# LoraGateway.net
KiCad netlist of a schematic drawn in EAGLE
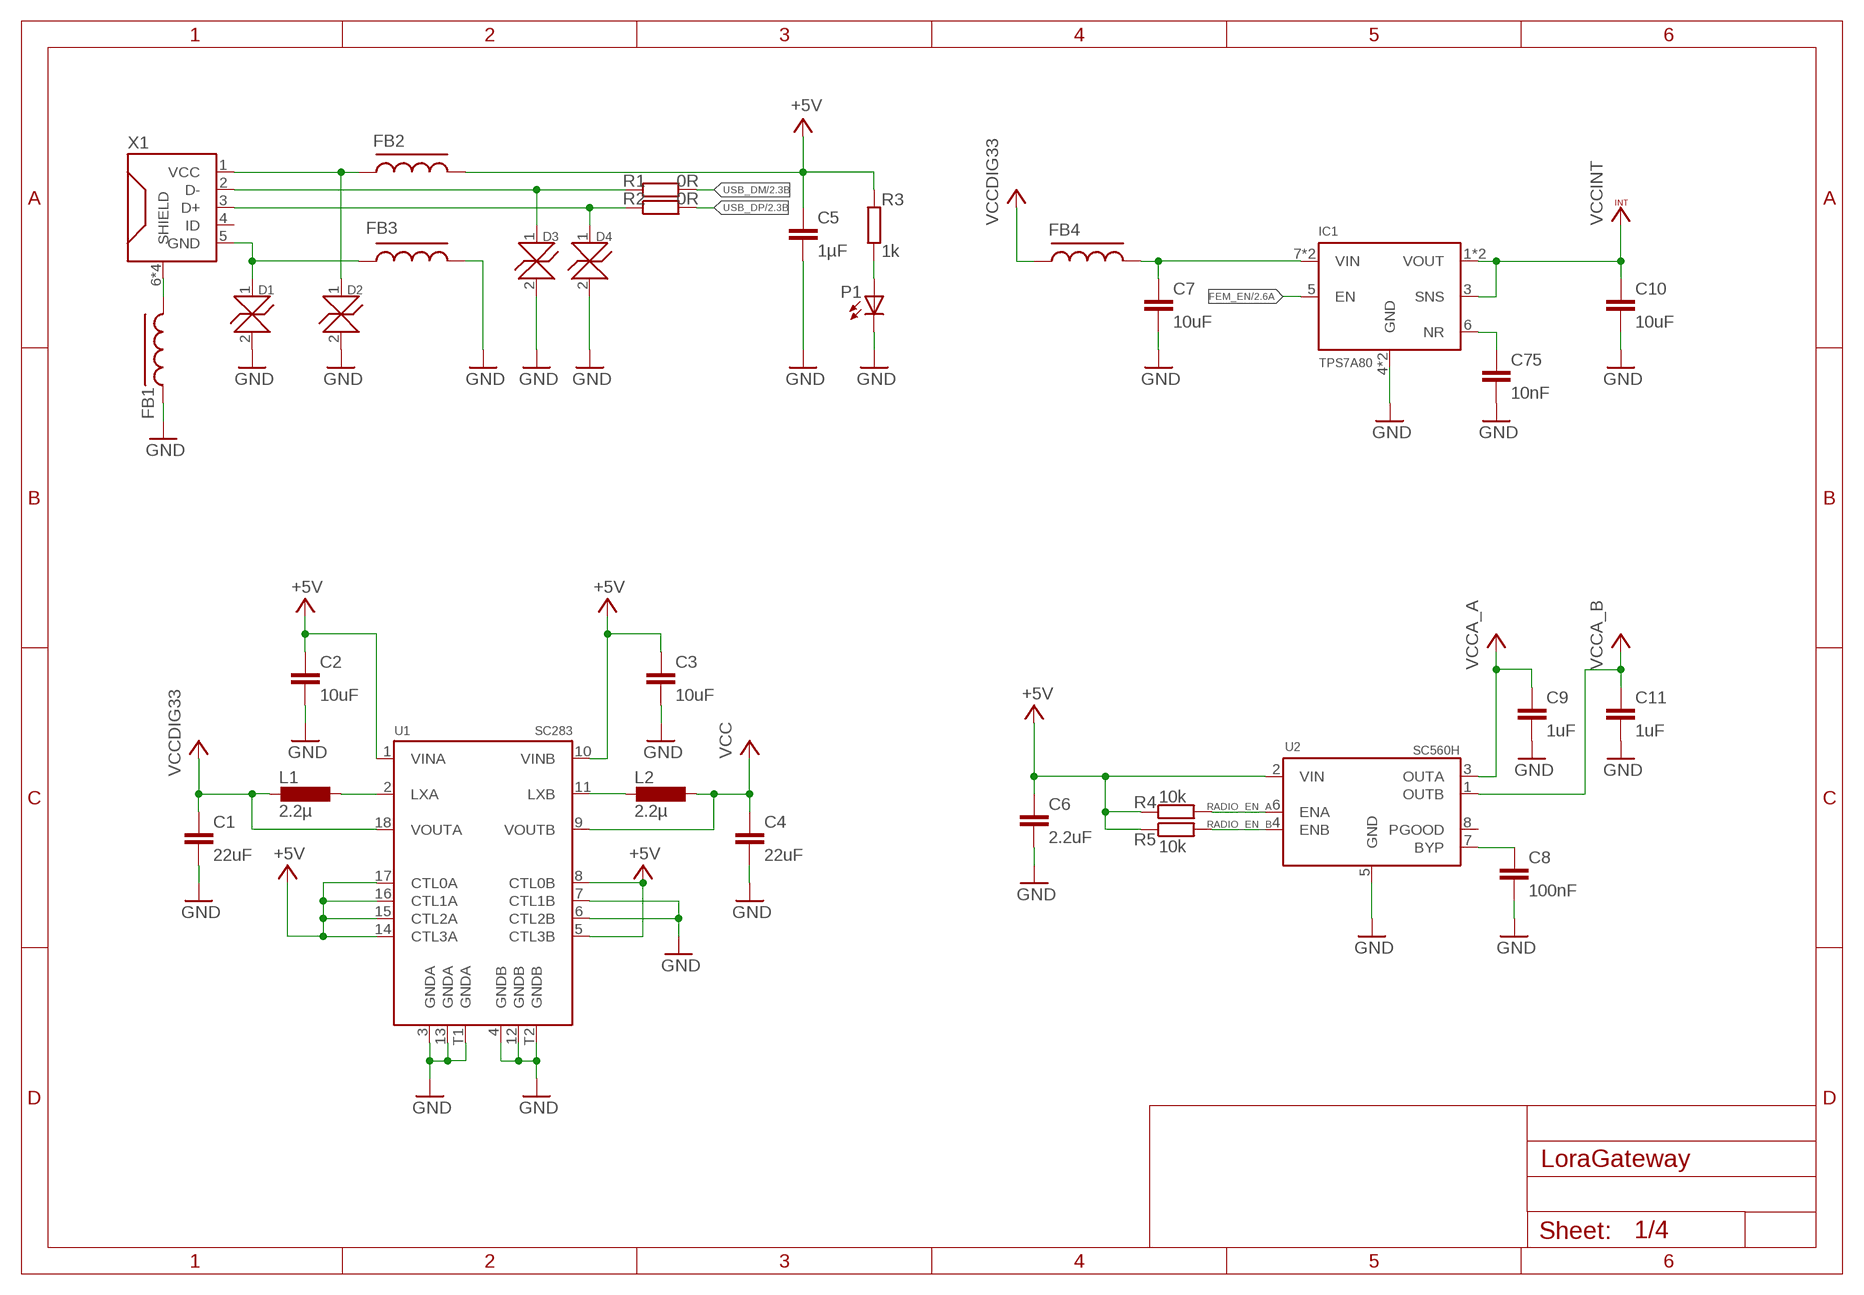
[diagram p0: schematic, sheet 1]
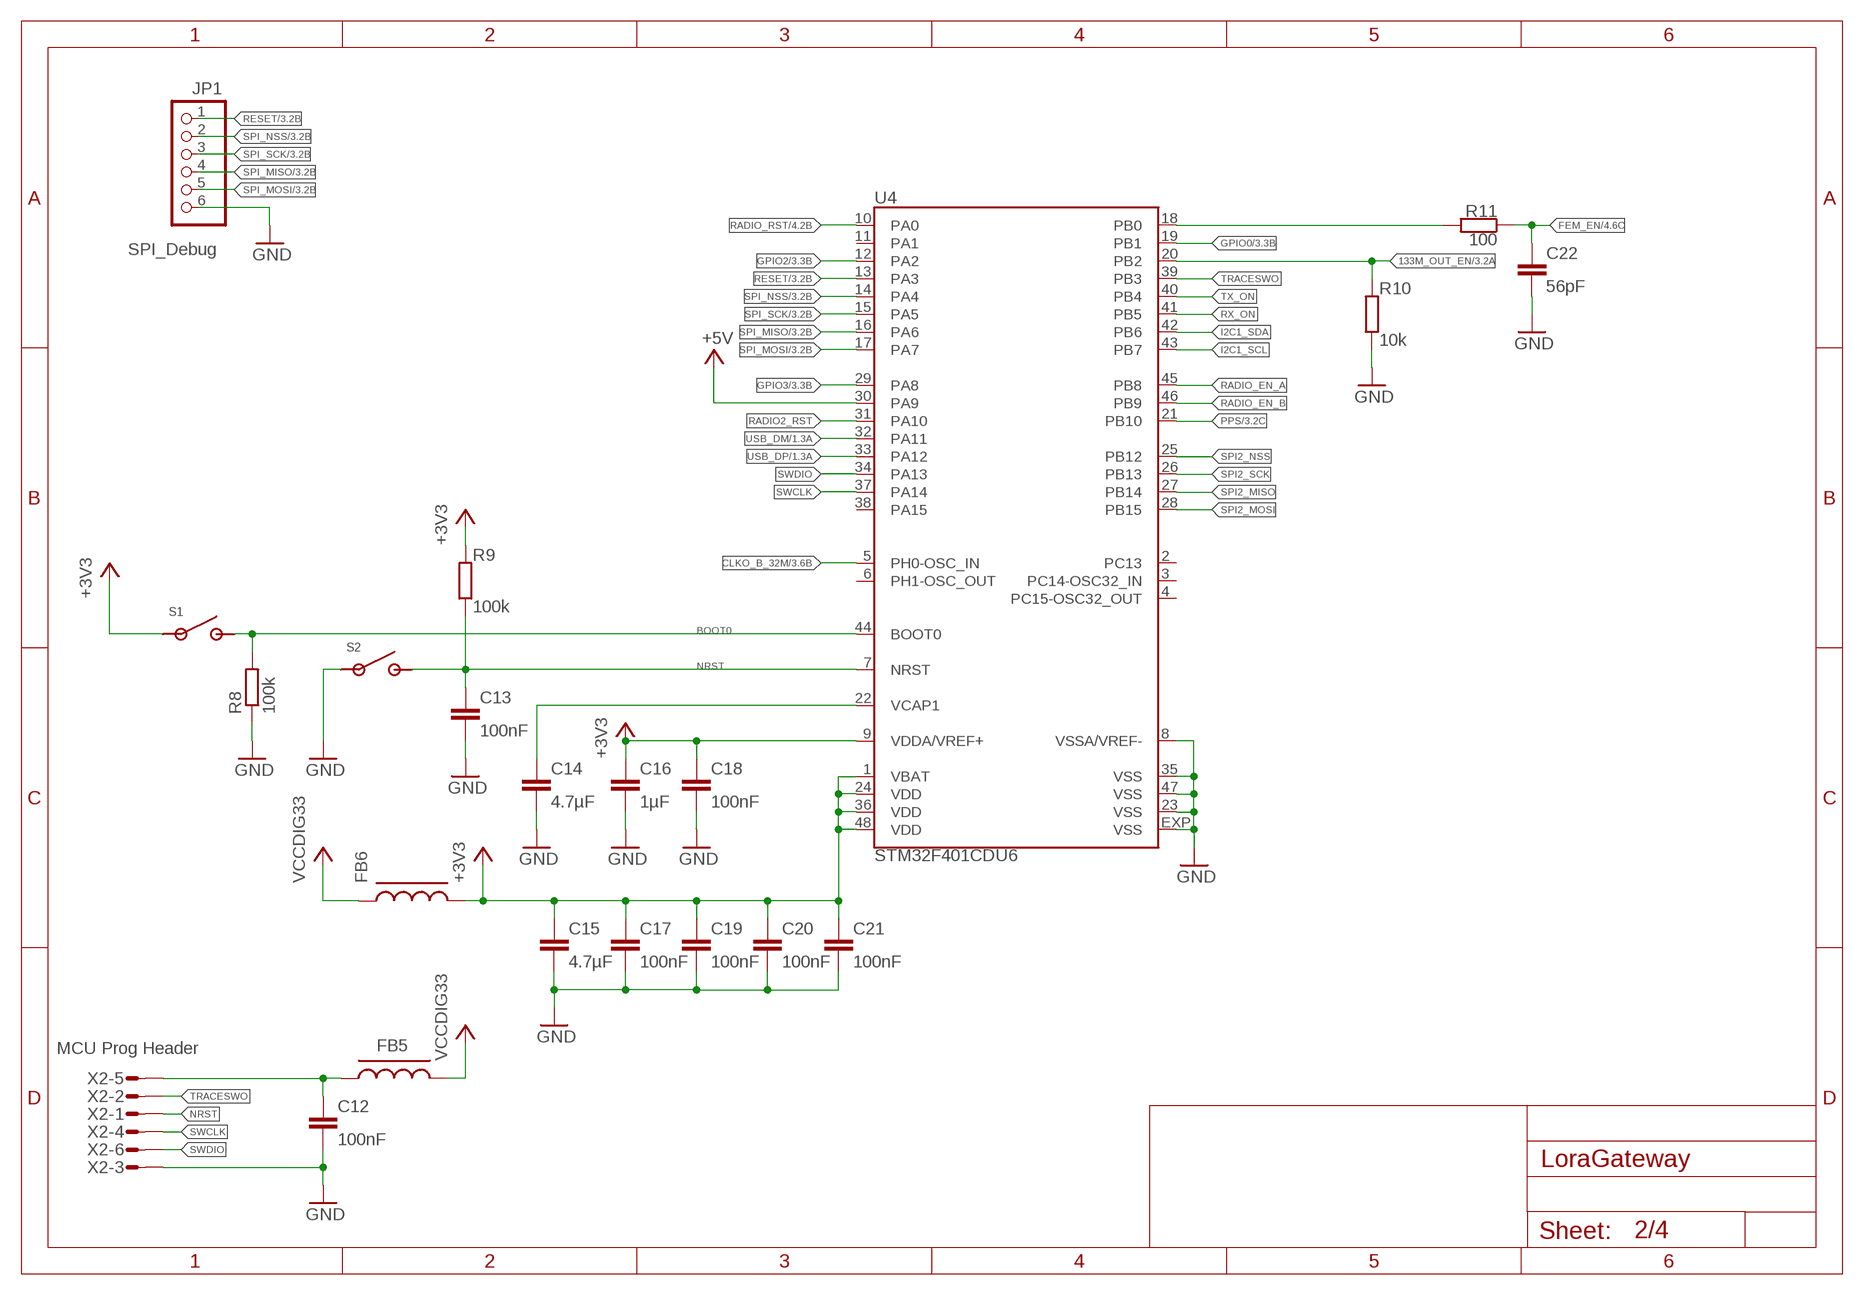
[diagram p1: schematic, sheet 2]
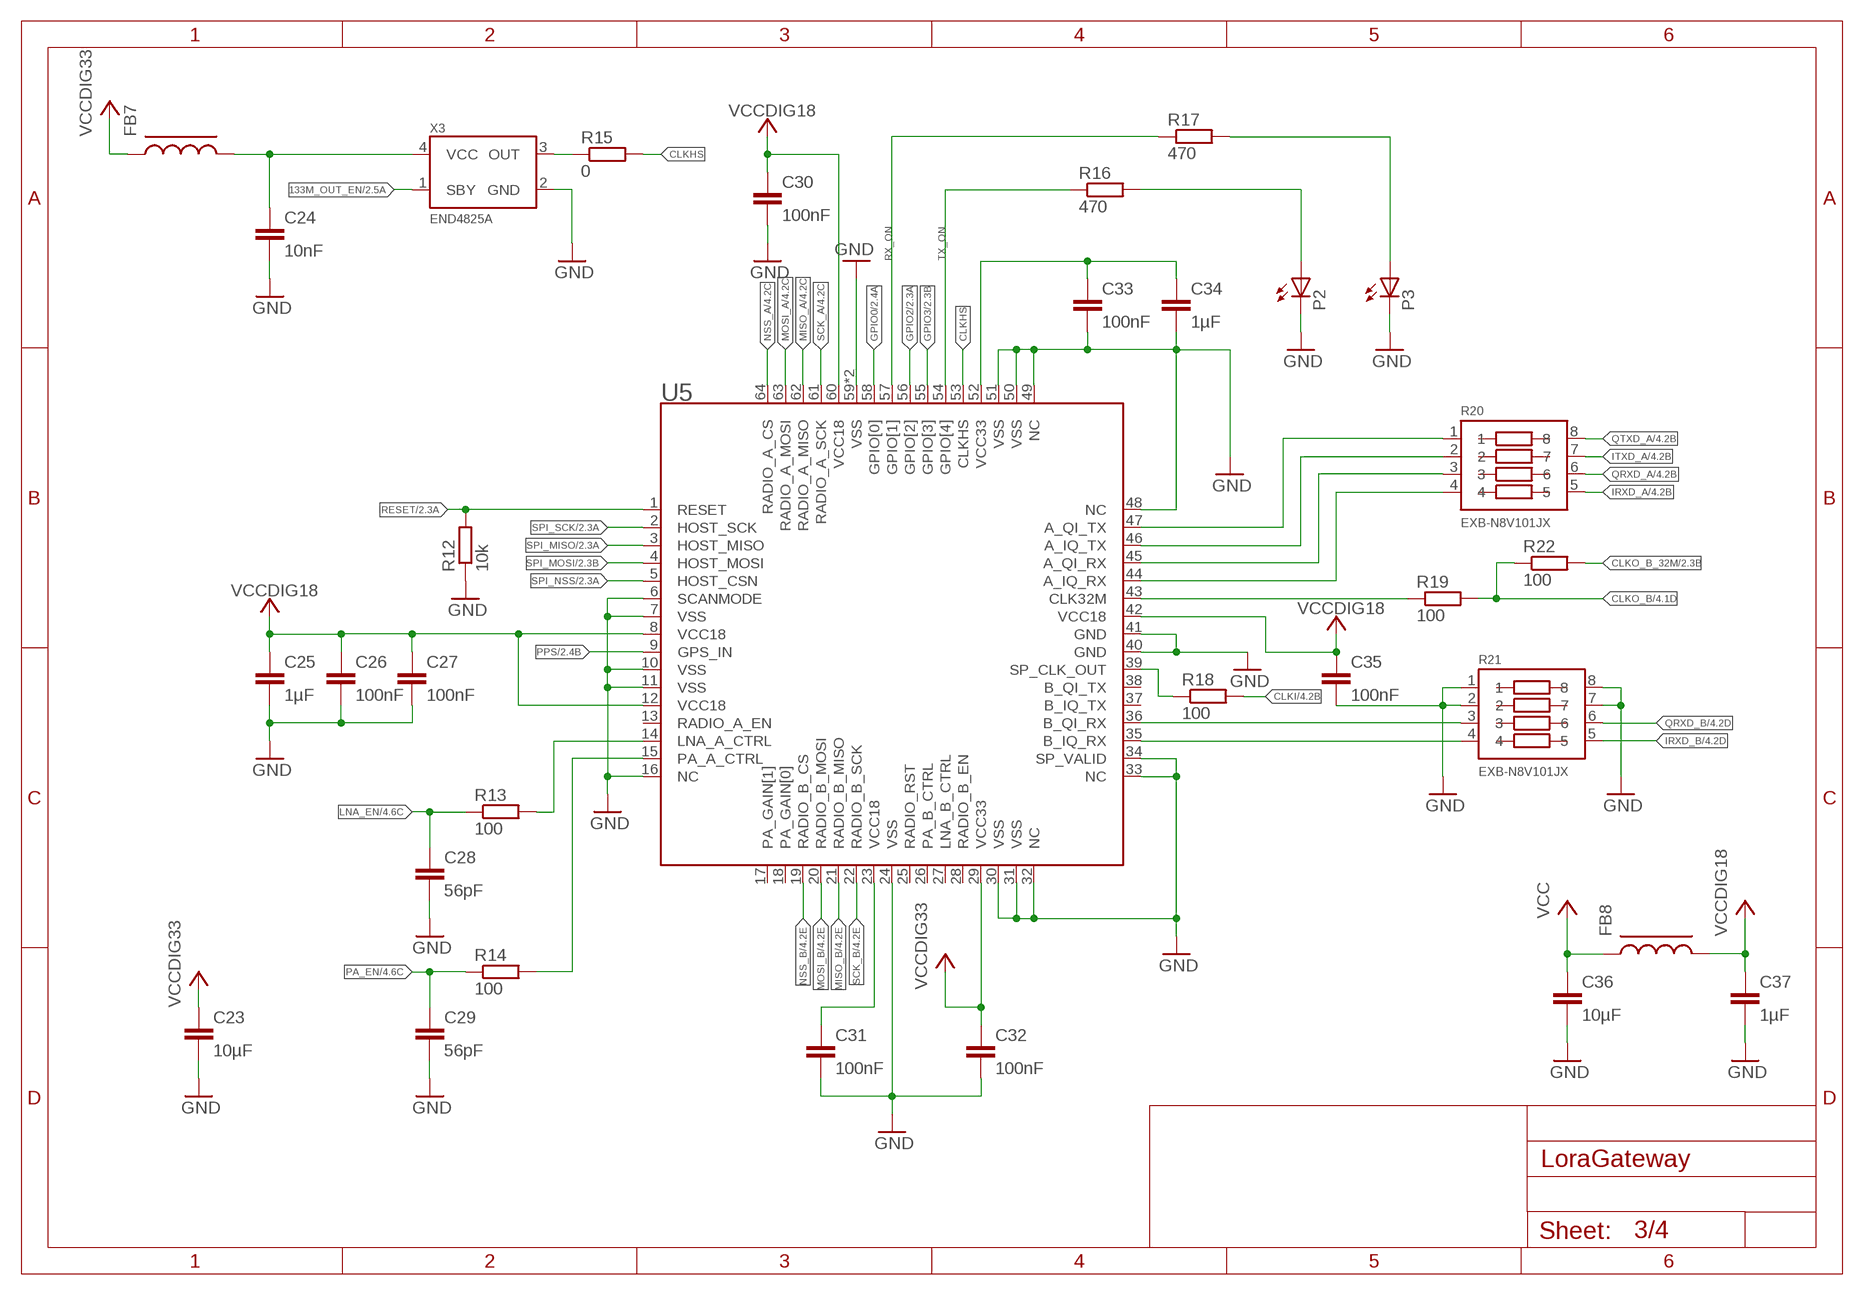
[diagram p2: schematic, sheet 3]
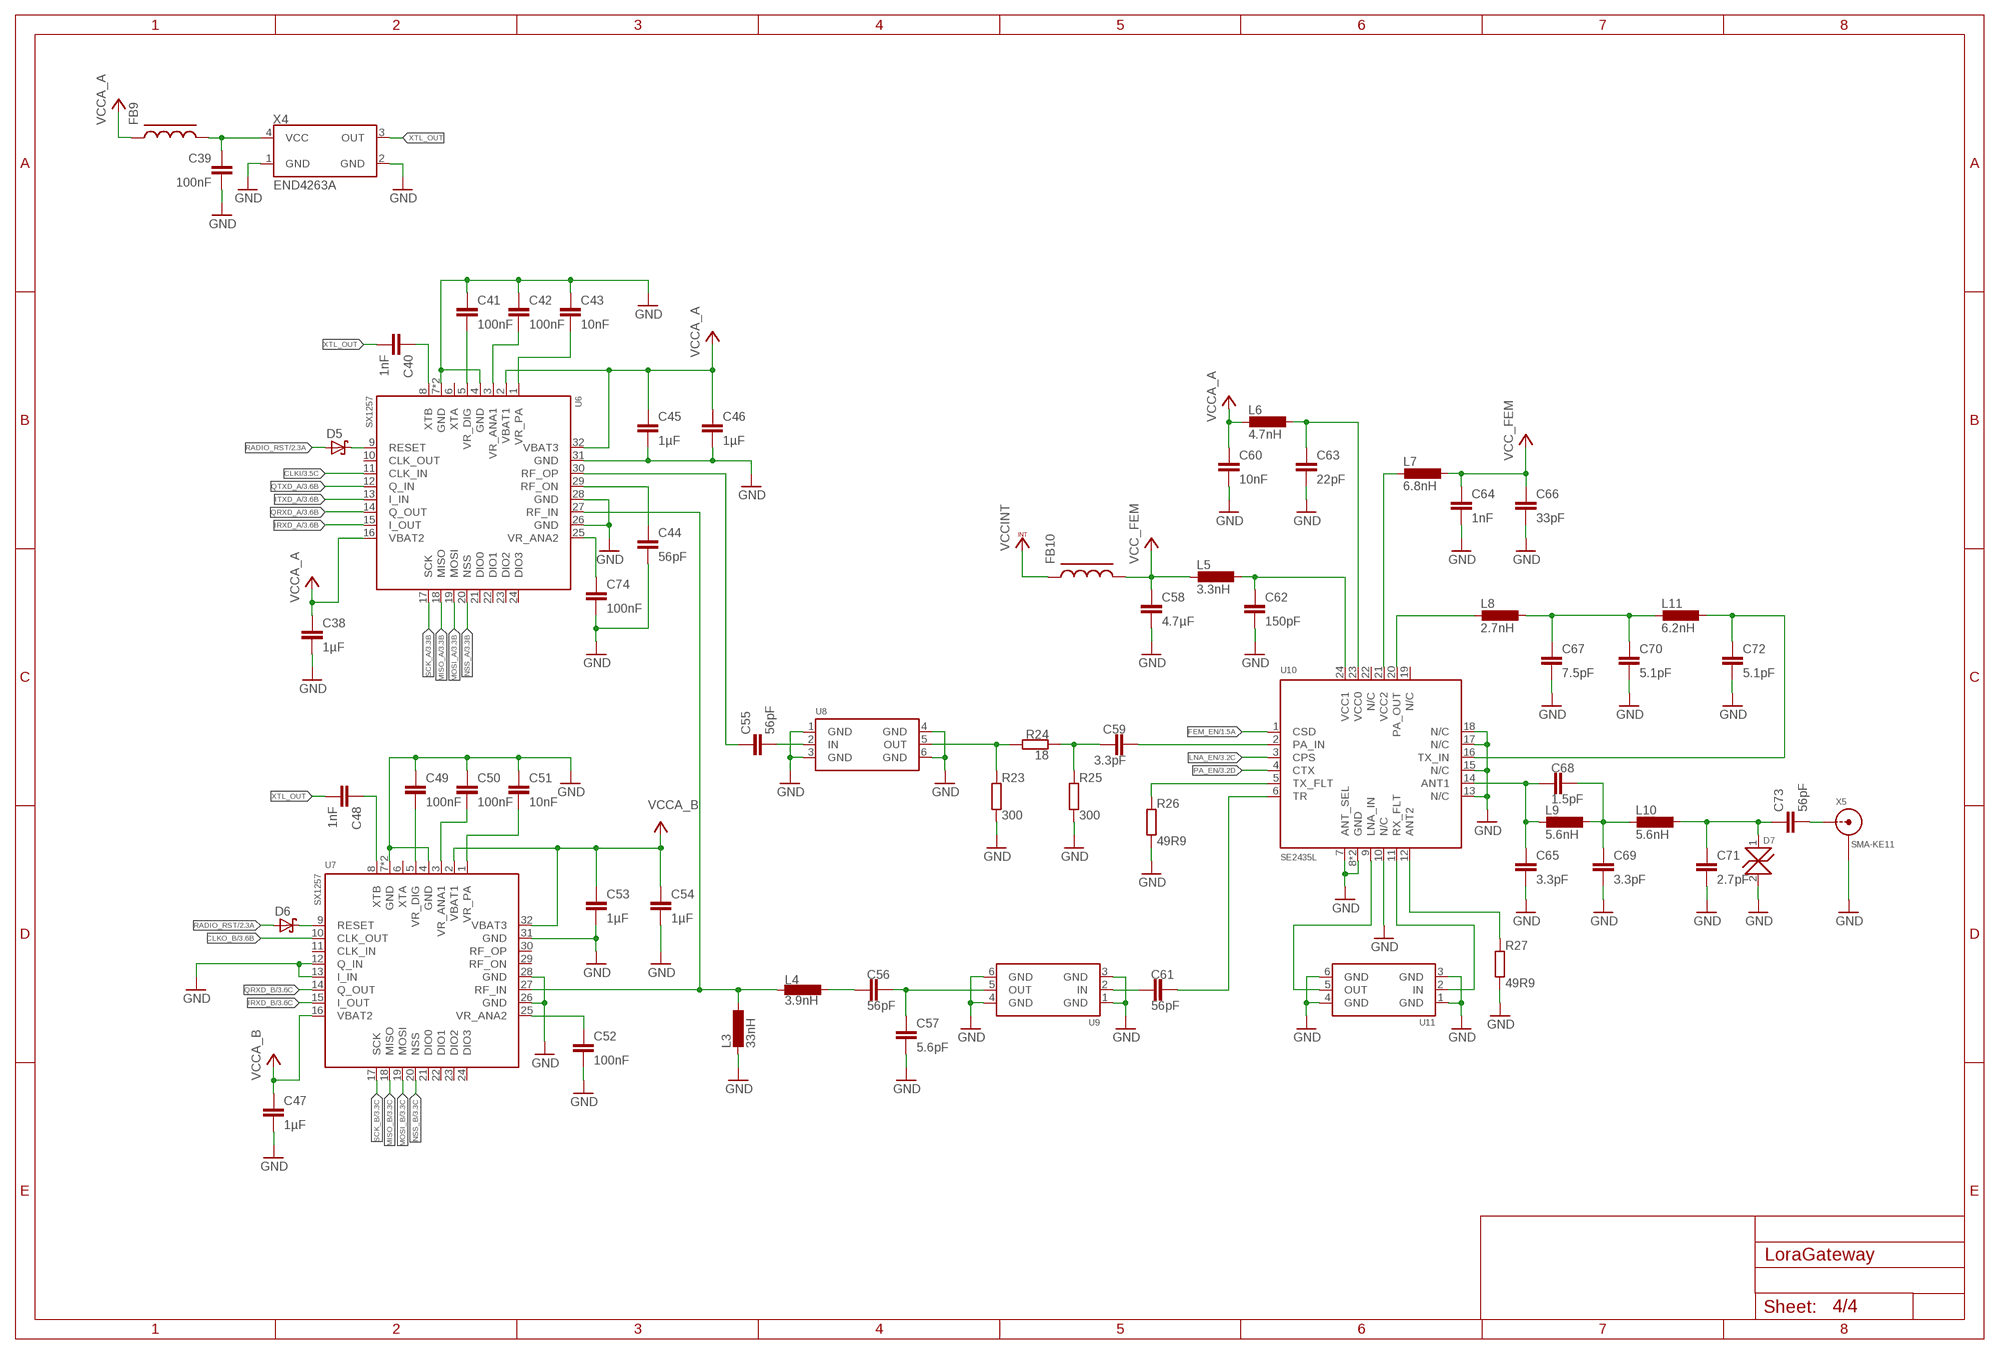
[diagram p3: schematic, sheet 4]

(export (version "E")
  (design (tool "Eeschema 10.0.6"))
  (components
    (comp (ref "C38")
      (value "1µF")
      (footprint "eagle-import:C0603")
      (libsource (lib "eagle-import") (part "C-EUC0603"))
    )
    (comp (ref "C39")
      (value "100nF")
      (footprint "eagle-import:C0402")
      (libsource (lib "eagle-import") (part "C-EUC0402"))
    )
    (comp (ref "C40")
      (value "1nF")
      (footprint "eagle-import:C0402")
      (fields (field (name "OC_DIGIKEY") "490-6348-1-ND"))
      (libsource (lib "eagle-import") (part "C-EUC0402"))
    )
    (comp (ref "C41")
      (value "100nF")
      (footprint "eagle-import:C0402")
      (libsource (lib "eagle-import") (part "C-EUC0402"))
    )
    (comp (ref "C42")
      (value "100nF")
      (footprint "eagle-import:C0402")
      (libsource (lib "eagle-import") (part "C-EUC0402"))
    )
    (comp (ref "C43")
      (value "10nF")
      (footprint "eagle-import:C0402")
      (libsource (lib "eagle-import") (part "C-EUC0402"))
    )
    (comp (ref "C44")
      (value "56pF")
      (footprint "eagle-import:C0402")
      (libsource (lib "eagle-import") (part "C-EUC0402"))
    )
    (comp (ref "C45")
      (value "1µF")
      (footprint "eagle-import:C0603")
      (libsource (lib "eagle-import") (part "C-EUC0603"))
    )
    (comp (ref "C46")
      (value "1µF")
      (footprint "eagle-import:C0603")
      (libsource (lib "eagle-import") (part "C-EUC0603"))
    )
    (comp (ref "C47")
      (value "1µF")
      (footprint "eagle-import:C0603")
      (libsource (lib "eagle-import") (part "C-EUC0603"))
    )
    (comp (ref "C48")
      (value "1nF")
      (footprint "eagle-import:C0402")
      (libsource (lib "eagle-import") (part "C-EUC0402"))
    )
    (comp (ref "C49")
      (value "100nF")
      (footprint "eagle-import:C0402")
      (libsource (lib "eagle-import") (part "C-EUC0402"))
    )
    (comp (ref "C50")
      (value "100nF")
      (footprint "eagle-import:C0402")
      (libsource (lib "eagle-import") (part "C-EUC0402"))
    )
    (comp (ref "C51")
      (value "10nF")
      (footprint "eagle-import:C0402")
      (libsource (lib "eagle-import") (part "C-EUC0402"))
    )
    (comp (ref "C52")
      (value "100nF")
      (footprint "eagle-import:C0402")
      (libsource (lib "eagle-import") (part "C-EUC0402"))
    )
    (comp (ref "C53")
      (value "1µF")
      (footprint "eagle-import:C0603")
      (libsource (lib "eagle-import") (part "C-EUC0603"))
    )
    (comp (ref "C54")
      (value "1µF")
      (footprint "eagle-import:C0603")
      (libsource (lib "eagle-import") (part "C-EUC0603"))
    )
    (comp (ref "C55")
      (value "56pF")
      (footprint "eagle-import:C0402")
      (libsource (lib "eagle-import") (part "C-EUC0402"))
    )
    (comp (ref "C56")
      (value "56pF")
      (footprint "eagle-import:C0402")
      (libsource (lib "eagle-import") (part "C-EUC0402"))
    )
    (comp (ref "C57")
      (value "5.6pF")
      (footprint "eagle-import:C0402")
      (libsource (lib "eagle-import") (part "C-EUC0402"))
    )
    (comp (ref "C58")
      (value "4.7µF")
      (footprint "eagle-import:C0603")
      (libsource (lib "eagle-import") (part "C-EUC0603"))
    )
    (comp (ref "C59")
      (value "3.3pF")
      (footprint "eagle-import:C0402")
      (libsource (lib "eagle-import") (part "C-EUC0402"))
    )
    (comp (ref "C60")
      (value "10nF")
      (footprint "eagle-import:C0402")
      (libsource (lib "eagle-import") (part "C-EUC0402"))
    )
    (comp (ref "C61")
      (value "56pF")
      (footprint "eagle-import:C0402")
      (libsource (lib "eagle-import") (part "C-EUC0402"))
    )
    (comp (ref "C62")
      (value "150pF")
      (footprint "eagle-import:C0402")
      (libsource (lib "eagle-import") (part "C-EUC0402"))
    )
    (comp (ref "C63")
      (value "22pF")
      (footprint "eagle-import:C0402")
      (libsource (lib "eagle-import") (part "C-EUC0402"))
    )
    (comp (ref "C64")
      (value "1nF")
      (footprint "eagle-import:C0402")
      (libsource (lib "eagle-import") (part "C-EUC0402"))
    )
    (comp (ref "C65")
      (value "3.3pF")
      (footprint "eagle-import:C0402")
      (libsource (lib "eagle-import") (part "C-EUC0402"))
    )
    (comp (ref "C66")
      (value "33pF")
      (footprint "eagle-import:C0402")
      (libsource (lib "eagle-import") (part "C-EUC0402"))
    )
    (comp (ref "C67")
      (value "7.5pF")
      (footprint "eagle-import:C0402")
      (libsource (lib "eagle-import") (part "C-EUC0402"))
    )
    (comp (ref "C68")
      (value "1.5pF")
      (footprint "eagle-import:C0402")
      (libsource (lib "eagle-import") (part "C-EUC0402"))
    )
    (comp (ref "C69")
      (value "3.3pF")
      (footprint "eagle-import:C0402")
      (libsource (lib "eagle-import") (part "C-EUC0402"))
    )
    (comp (ref "C70")
      (value "5.1pF")
      (footprint "eagle-import:C0402")
      (libsource (lib "eagle-import") (part "C-EUC0402"))
    )
    (comp (ref "C71")
      (value "2.7pF")
      (footprint "eagle-import:C0402")
      (libsource (lib "eagle-import") (part "C-EUC0402"))
    )
    (comp (ref "C72")
      (value "5.1pF")
      (footprint "eagle-import:C0402")
      (libsource (lib "eagle-import") (part "C-EUC0402"))
    )
    (comp (ref "C73")
      (value "56pF")
      (footprint "eagle-import:C0402")
      (libsource (lib "eagle-import") (part "C-EUC0402"))
    )
    (comp (ref "C74")
      (value "100nF")
      (footprint "eagle-import:C0402")
      (libsource (lib "eagle-import") (part "C-EUC0402"))
    )
    (comp (ref "D5")
      (value "BAT54XV2T1G")
      (footprint "eagle-import:SOD523")
      (libsource (lib "eagle-import") (part "BAT54XV2T1G"))
    )
    (comp (ref "D6")
      (value "BAT54XV2T1G")
      (footprint "eagle-import:SOD523")
      (libsource (lib "eagle-import") (part "BAT54XV2T1G"))
    )
    (comp (ref "D7")
      (value "LXES15AAA1-153")
      (footprint "eagle-import:LXES15AAA1-153")
      (libsource (lib "eagle-import") (part "LXES15AAA1-153"))
    )
    (comp (ref "FB9")
      (value "BLM15PG100SN1D0402")
      (footprint "eagle-import:L0402")
      (libsource (lib "eagle-import") (part "BLM15PG100SN1D0402"))
    )
    (comp (ref "FB10")
      (value "BLM18PG121SH1D")
      (footprint "eagle-import:L0603")
      (libsource (lib "eagle-import") (part "BLM18PG121SH1D"))
    )
    (comp (ref "L3")
      (value "33nH")
      (footprint "eagle-import:L0402")
      (libsource (lib "eagle-import") (part "L-EU0402"))
    )
    (comp (ref "L4")
      (value "3.9nH")
      (footprint "eagle-import:L0402")
      (libsource (lib "eagle-import") (part "L-EU0402"))
    )
    (comp (ref "L5")
      (value "3.3nH")
      (footprint "eagle-import:L0402")
      (libsource (lib "eagle-import") (part "L-EU0402"))
    )
    (comp (ref "L6")
      (value "4.7nH")
      (footprint "eagle-import:L0402")
      (libsource (lib "eagle-import") (part "L-EU0402"))
    )
    (comp (ref "L7")
      (value "6.8nH")
      (footprint "eagle-import:L0402")
      (libsource (lib "eagle-import") (part "L-EU0402"))
    )
    (comp (ref "L8")
      (value "2.7nH")
      (footprint "eagle-import:L0402")
      (libsource (lib "eagle-import") (part "L-EU0402"))
    )
    (comp (ref "L9")
      (value "5.6nH")
      (footprint "eagle-import:L0402")
      (libsource (lib "eagle-import") (part "L-EU0402"))
    )
    (comp (ref "L10")
      (value "5.6nH")
      (footprint "eagle-import:L0402")
      (libsource (lib "eagle-import") (part "L-EU0402"))
    )
    (comp (ref "L11")
      (value "6.2nH")
      (footprint "eagle-import:L0402")
      (libsource (lib "eagle-import") (part "L-EU0402"))
    )
    (comp (ref "R23")
      (value "300")
      (footprint "eagle-import:R0402")
      (libsource (lib "eagle-import") (part "R-EU_R0402"))
    )
    (comp (ref "R24")
      (value "18")
      (footprint "eagle-import:R0402")
      (libsource (lib "eagle-import") (part "R-EU_R0402"))
    )
    (comp (ref "R25")
      (value "300")
      (footprint "eagle-import:R0402")
      (libsource (lib "eagle-import") (part "R-EU_R0402"))
    )
    (comp (ref "R26")
      (value "49R9")
      (footprint "eagle-import:R0402")
      (libsource (lib "eagle-import") (part "R-EU_R0402"))
    )
    (comp (ref "R27")
      (value "49R9")
      (footprint "eagle-import:R0402")
      (libsource (lib "eagle-import") (part "R-EU_R0402"))
    )
    (comp (ref "U6")
      (value "SX1257")
      (footprint "eagle-import:QFN32")
      (libsource (lib "eagle-import") (part "SX1257"))
    )
    (comp (ref "U7")
      (value "SX1257")
      (footprint "eagle-import:QFN32")
      (libsource (lib "eagle-import") (part "SX1257"))
    )
    (comp (ref "U8")
      (value "B39871B3717U410")
      (footprint "eagle-import:DCC6C-3X3")
      (libsource (lib "eagle-import") (part "B39871B3717U410"))
    )
    (comp (ref "U9")
      (value "B39871B3717U410")
      (footprint "eagle-import:DCC6C-3X3")
      (libsource (lib "eagle-import") (part "B39871B3717U410"))
    )
    (comp (ref "U10")
      (value "SE2435L")
      (footprint "eagle-import:VQFN24-4X4")
      (libsource (lib "eagle-import") (part "SE2435L"))
    )
    (comp (ref "U11")
      (value "B39871B3717U410")
      (footprint "eagle-import:DCC6C-3X3")
      (libsource (lib "eagle-import") (part "B39871B3717U410"))
    )
    (comp (ref "X4")
      (value "END4263A")
      (footprint "eagle-import:2.0X1.6MM")
      (libsource (lib "eagle-import") (part "END4263A"))
    )
    (comp (ref "X5")
      (value "SMA-KE11")
      (footprint "eagle-import:J502-ND-142-0711-871_876")
      (libsource (lib "eagle-import") (part "SMA-KE11"))
    )
    (comp (ref "C1")
      (value "22uF")
      (footprint "eagle-import:C1206")
      (libsource (lib "eagle-import") (part "C-EUC1206"))
    )
    (comp (ref "C2")
      (value "10uF")
      (footprint "eagle-import:C1206")
      (libsource (lib "eagle-import") (part "C-EUC1206"))
    )
    (comp (ref "C3")
      (value "10uF")
      (footprint "eagle-import:C1206")
      (libsource (lib "eagle-import") (part "C-EUC1206"))
    )
    (comp (ref "C4")
      (value "22uF")
      (footprint "eagle-import:C1206")
      (libsource (lib "eagle-import") (part "C-EUC1206"))
    )
    (comp (ref "C5")
      (value "1µF")
      (footprint "eagle-import:C0805")
      (libsource (lib "eagle-import") (part "C-EUC0805"))
    )
    (comp (ref "C6")
      (value "2.2uF")
      (footprint "eagle-import:C0603")
      (libsource (lib "eagle-import") (part "C-EUC0603"))
    )
    (comp (ref "C7")
      (value "10uF")
      (footprint "eagle-import:C0805")
      (libsource (lib "eagle-import") (part "C-EUC0805"))
    )
    (comp (ref "C8")
      (value "100nF")
      (footprint "eagle-import:C0402")
      (libsource (lib "eagle-import") (part "C-EUC0402"))
    )
    (comp (ref "C9")
      (value "1uF")
      (footprint "eagle-import:C0805")
      (libsource (lib "eagle-import") (part "C-EUC0805"))
    )
    (comp (ref "C10")
      (value "10uF")
      (footprint "eagle-import:C0805")
      (libsource (lib "eagle-import") (part "C-EUC0805"))
    )
    (comp (ref "C11")
      (value "1uF")
      (footprint "eagle-import:C0805")
      (libsource (lib "eagle-import") (part "C-EUC0805"))
    )
    (comp (ref "C75")
      (value "10nF")
      (footprint "eagle-import:C0402")
      (libsource (lib "eagle-import") (part "C-EUC0402"))
    )
    (comp (ref "D1")
      (value "RCLAMP0531T")
      (footprint "eagle-import:SLP1006P2T")
      (libsource (lib "eagle-import") (part "RCLAMP0531T"))
    )
    (comp (ref "D2")
      (value "RCLAMP0531T")
      (footprint "eagle-import:SLP1006P2T")
      (libsource (lib "eagle-import") (part "RCLAMP0531T"))
    )
    (comp (ref "D3")
      (value "RCLAMP0531T")
      (footprint "eagle-import:SLP1006P2T")
      (libsource (lib "eagle-import") (part "RCLAMP0531T"))
    )
    (comp (ref "D4")
      (value "RCLAMP0531T")
      (footprint "eagle-import:SLP1006P2T")
      (libsource (lib "eagle-import") (part "RCLAMP0531T"))
    )
    (comp (ref "FB1")
      (value "BLM15PG100SN1D0402")
      (footprint "eagle-import:L0402")
      (libsource (lib "eagle-import") (part "BLM15PG100SN1D0402"))
    )
    (comp (ref "FB2")
      (value "BLM15PG100SN1D0402")
      (footprint "eagle-import:L0402")
      (libsource (lib "eagle-import") (part "BLM15PG100SN1D0402"))
    )
    (comp (ref "FB3")
      (value "BLM15PG100SN1D0402")
      (footprint "eagle-import:L0402")
      (libsource (lib "eagle-import") (part "BLM15PG100SN1D0402"))
    )
    (comp (ref "FB4")
      (value "BLM15PG100SN1D0402")
      (footprint "eagle-import:L0402")
      (libsource (lib "eagle-import") (part "BLM15PG100SN1D0402"))
    )
    (comp (ref "IC1")
      (value "TPS7A80")
      (footprint "eagle-import:SON-8")
      (libsource (lib "eagle-import") (part "TPS7A80"))
    )
    (comp (ref "L1")
      (value "2.2µ")
      (footprint "eagle-import:ASPI-0418")
      (libsource (lib "eagle-import") (part "ASPI-0418"))
    )
    (comp (ref "L2")
      (value "2.2µ")
      (footprint "eagle-import:ASPI-0418")
      (libsource (lib "eagle-import") (part "ASPI-0418"))
    )
    (comp (ref "P1")
      (value "LTST-C191KGKT")
      (footprint "eagle-import:LED_SML0603")
      (libsource (lib "eagle-import") (part "LTST-C191KGKT"))
    )
    (comp (ref "R1")
      (value "0R")
      (footprint "eagle-import:R0402")
      (libsource (lib "eagle-import") (part "R-EU_R0402"))
    )
    (comp (ref "R2")
      (value "0R")
      (footprint "eagle-import:R0402")
      (libsource (lib "eagle-import") (part "R-EU_R0402"))
    )
    (comp (ref "R3")
      (value "1k")
      (footprint "eagle-import:R0402")
      (libsource (lib "eagle-import") (part "R-EU_R0402"))
    )
    (comp (ref "R4")
      (value "10k")
      (footprint "eagle-import:R0402")
      (libsource (lib "eagle-import") (part "R-EU_R0402"))
    )
    (comp (ref "R5")
      (value "10k")
      (footprint "eagle-import:R0402")
      (libsource (lib "eagle-import") (part "R-EU_R0402"))
    )
    (comp (ref "U1")
      (value "SC283")
      (footprint "eagle-import:2X3MLPQ-W18")
      (libsource (lib "eagle-import") (part "SC283"))
    )
    (comp (ref "U2")
      (value "SC560H")
      (footprint "eagle-import:MLPQ-UT8")
      (libsource (lib "eagle-import") (part "SC560H"))
    )
    (comp (ref "X1")
      (value "USB2-MICRO")
      (footprint "eagle-import:USB-2-MICRO")
      (libsource (lib "eagle-import") (part "USB2-MICRO"))
    )
    (comp (ref "C23")
      (value "10µF")
      (footprint "eagle-import:C0805")
      (libsource (lib "eagle-import") (part "C-EUC0805"))
    )
    (comp (ref "C24")
      (value "10nF")
      (footprint "eagle-import:C0402")
      (libsource (lib "eagle-import") (part "C-EUC0402"))
    )
    (comp (ref "C25")
      (value "1µF")
      (footprint "eagle-import:C0603")
      (libsource (lib "eagle-import") (part "C-EUC0603"))
    )
    (comp (ref "C26")
      (value "100nF")
      (footprint "eagle-import:C0402")
      (libsource (lib "eagle-import") (part "C-EUC0402"))
    )
    (comp (ref "C27")
      (value "100nF")
      (footprint "eagle-import:C0402")
      (libsource (lib "eagle-import") (part "C-EUC0402"))
    )
    (comp (ref "C28")
      (value "56pF")
      (footprint "eagle-import:C0402")
      (libsource (lib "eagle-import") (part "C-EUC0402"))
    )
    (comp (ref "C29")
      (value "56pF")
      (footprint "eagle-import:C0402")
      (libsource (lib "eagle-import") (part "C-EUC0402"))
    )
    (comp (ref "C30")
      (value "100nF")
      (footprint "eagle-import:C0402")
      (libsource (lib "eagle-import") (part "C-EUC0402"))
    )
    (comp (ref "C31")
      (value "100nF")
      (footprint "eagle-import:C0402")
      (libsource (lib "eagle-import") (part "C-EUC0402"))
    )
    (comp (ref "C32")
      (value "100nF")
      (footprint "eagle-import:C0402")
      (libsource (lib "eagle-import") (part "C-EUC0402"))
    )
    (comp (ref "C33")
      (value "100nF")
      (footprint "eagle-import:C0402")
      (libsource (lib "eagle-import") (part "C-EUC0402"))
    )
    (comp (ref "C34")
      (value "1µF")
      (footprint "eagle-import:C0603")
      (libsource (lib "eagle-import") (part "C-EUC0603"))
    )
    (comp (ref "C35")
      (value "100nF")
      (footprint "eagle-import:C0402")
      (libsource (lib "eagle-import") (part "C-EUC0402"))
    )
    (comp (ref "C36")
      (value "10µF")
      (footprint "eagle-import:C0805")
      (libsource (lib "eagle-import") (part "C-EUC0805"))
    )
    (comp (ref "C37")
      (value "1µF")
      (footprint "eagle-import:C0603")
      (libsource (lib "eagle-import") (part "C-EUC0603"))
    )
    (comp (ref "FB7")
      (value "BLM15PG100SN1D0402")
      (footprint "eagle-import:L0402")
      (libsource (lib "eagle-import") (part "BLM15PG100SN1D0402"))
    )
    (comp (ref "FB8")
      (value "BLM15PG100SN1D0402")
      (footprint "eagle-import:L0402")
      (libsource (lib "eagle-import") (part "BLM15PG100SN1D0402"))
    )
    (comp (ref "P2")
      (value "LTST-C930KGKT")
      (footprint "eagle-import:LTST-C930KGKT")
      (libsource (lib "eagle-import") (part "LTST-C930KGKT"))
    )
    (comp (ref "P3")
      (value "LTST-C930KGKT")
      (footprint "eagle-import:LTST-C930KGKT")
      (libsource (lib "eagle-import") (part "LTST-C930KGKT"))
    )
    (comp (ref "R12")
      (value "10k")
      (footprint "eagle-import:R0402")
      (libsource (lib "eagle-import") (part "R-EU_R0402"))
    )
    (comp (ref "R13")
      (value "100")
      (footprint "eagle-import:R0402")
      (libsource (lib "eagle-import") (part "R-EU_R0402"))
    )
    (comp (ref "R14")
      (value "100")
      (footprint "eagle-import:R0402")
      (libsource (lib "eagle-import") (part "R-EU_R0402"))
    )
    (comp (ref "R15")
      (value "0")
      (footprint "eagle-import:R0402")
      (libsource (lib "eagle-import") (part "R-EU_R0402"))
    )
    (comp (ref "R16")
      (value "470")
      (footprint "eagle-import:R0402")
      (libsource (lib "eagle-import") (part "R-EU_R0402"))
    )
    (comp (ref "R17")
      (value "470")
      (footprint "eagle-import:R0402")
      (libsource (lib "eagle-import") (part "R-EU_R0402"))
    )
    (comp (ref "R18")
      (value "100")
      (footprint "eagle-import:R0402")
      (libsource (lib "eagle-import") (part "R-EU_R0402"))
    )
    (comp (ref "R19")
      (value "100")
      (footprint "eagle-import:R0402")
      (libsource (lib "eagle-import") (part "R-EU_R0402"))
    )
    (comp (ref "R20")
      (value "EXB-N8V101JX")
      (footprint "eagle-import:EXB28V")
      (libsource (lib "eagle-import") (part "EXB-N8V101JX"))
    )
    (comp (ref "R21")
      (value "EXB-N8V101JX")
      (footprint "eagle-import:EXB28V")
      (libsource (lib "eagle-import") (part "EXB-N8V101JX"))
    )
    (comp (ref "R22")
      (value "100")
      (footprint "eagle-import:R0402")
      (libsource (lib "eagle-import") (part "R-EU_R0402"))
    )
    (comp (ref "U5")
      (value "SX1308")
      (footprint "eagle-import:QFN64-9X9")
      (libsource (lib "eagle-import") (part "SX1308"))
    )
    (comp (ref "X3")
      (value "END4825A")
      (footprint "eagle-import:2.5X2.0MM")
      (libsource (lib "eagle-import") (part "END4825A"))
    )
    (comp (ref "C12")
      (value "100nF")
      (footprint "eagle-import:C0402")
      (libsource (lib "eagle-import") (part "C-EUC0402"))
    )
    (comp (ref "C13")
      (value "100nF")
      (footprint "eagle-import:C0402")
      (libsource (lib "eagle-import") (part "C-EUC0402"))
    )
    (comp (ref "C14")
      (value "4.7µF")
      (footprint "eagle-import:C0603")
      (libsource (lib "eagle-import") (part "C-EUC0603"))
    )
    (comp (ref "C15")
      (value "4.7µF")
      (footprint "eagle-import:C0603")
      (libsource (lib "eagle-import") (part "C-EUC0603"))
    )
    (comp (ref "C16")
      (value "1µF")
      (footprint "eagle-import:C0402")
      (libsource (lib "eagle-import") (part "C-EUC0402"))
    )
    (comp (ref "C17")
      (value "100nF")
      (footprint "eagle-import:C0402")
      (libsource (lib "eagle-import") (part "C-EUC0402"))
    )
    (comp (ref "C18")
      (value "100nF")
      (footprint "eagle-import:C0402")
      (libsource (lib "eagle-import") (part "C-EUC0402"))
    )
    (comp (ref "C19")
      (value "100nF")
      (footprint "eagle-import:C0402")
      (libsource (lib "eagle-import") (part "C-EUC0402"))
    )
    (comp (ref "C20")
      (value "100nF")
      (footprint "eagle-import:C0402")
      (libsource (lib "eagle-import") (part "C-EUC0402"))
    )
    (comp (ref "C21")
      (value "100nF")
      (footprint "eagle-import:C0402")
      (libsource (lib "eagle-import") (part "C-EUC0402"))
    )
    (comp (ref "C22")
      (value "56pF")
      (footprint "eagle-import:C0402")
      (libsource (lib "eagle-import") (part "C-EUC0402"))
    )
    (comp (ref "FB5")
      (value "BLM15PG100SN1D0402")
      (footprint "eagle-import:L0402")
      (libsource (lib "eagle-import") (part "BLM15PG100SN1D0402"))
    )
    (comp (ref "FB6")
      (value "BLM15PG100SN1D0402")
      (footprint "eagle-import:L0402")
      (libsource (lib "eagle-import") (part "BLM15PG100SN1D0402"))
    )
    (comp (ref "JP1")
      (value "SPI_Debug")
      (footprint "eagle-import:1X06")
      (libsource (lib "eagle-import") (part "PINHD-1X6"))
    )
    (comp (ref "R8")
      (value "100k")
      (footprint "eagle-import:R0402")
      (libsource (lib "eagle-import") (part "R-EU_R0402"))
    )
    (comp (ref "R9")
      (value "100k")
      (footprint "eagle-import:R0402")
      (libsource (lib "eagle-import") (part "R-EU_R0402"))
    )
    (comp (ref "R10")
      (value "10k")
      (footprint "eagle-import:R0402")
      (libsource (lib "eagle-import") (part "R-EU_R0402"))
    )
    (comp (ref "R11")
      (value "100")
      (footprint "eagle-import:R0402")
      (libsource (lib "eagle-import") (part "R-EU_R0402"))
    )
    (comp (ref "S1")
      (value "KXT121LHS")
      (footprint "eagle-import:SMDSWITCH3.5X2.0MM")
      (libsource (lib "eagle-import") (part "KXT121LHS"))
    )
    (comp (ref "S2")
      (value "KXT121LHS")
      (footprint "eagle-import:SMDSWITCH3.5X2.0MM")
      (libsource (lib "eagle-import") (part "KXT121LHS"))
    )
    (comp (ref "U4")
      (value "STM32F401CDU6")
      (footprint "eagle-import:P-QFP48-7X7MM")
      (libsource (lib "eagle-import") (part "STM32F401CDU6"))
    )
    (comp (ref "X2")
      (value "MCU Prog Header")
      (footprint "eagle-import:MICROMATCH-6")
      (fields
        (field (name "MPN") "7-215464-6")
        (field (name "DIGIKEY") "A99463TR-ND")
        (field (name "OC_DIGIKEY") "A30729TR-ND")
      )
      (libsource (lib "eagle-import") (part "MICROMATCH-6"))
    )
  )
  (nets
    (net (code "1") (name "+3V3") (class "Default")
      (node (ref "C15") (pin "1") (pinfunction "1_1") (pintype "passive"))
      (node (ref "C16") (pin "1") (pinfunction "1_1") (pintype "passive"))
      (node (ref "C17") (pin "1") (pinfunction "1_1") (pintype "passive"))
      (node (ref "C18") (pin "1") (pinfunction "1_1") (pintype "passive"))
      (node (ref "C19") (pin "1") (pinfunction "1_1") (pintype "passive"))
      (node (ref "C20") (pin "1") (pinfunction "1_1") (pintype "passive"))
      (node (ref "C21") (pin "1") (pinfunction "1_1") (pintype "passive"))
      (node (ref "FB6") (pin "2") (pinfunction "2_2") (pintype "passive"))
      (node (ref "R9") (pin "2") (pinfunction "2_2") (pintype "passive"))
      (node (ref "S1") (pin "P$1") (pinfunction "1_P$1") (pintype "bidirectional"))
      (node (ref "U4") (pin "1") (pinfunction "VBAT_1") (pintype "bidirectional"))
      (node (ref "U4") (pin "24") (pinfunction "VDD_24") (pintype "bidirectional"))
      (node (ref "U4") (pin "36") (pinfunction "VDD_36") (pintype "bidirectional"))
      (node (ref "U4") (pin "48") (pinfunction "VDD_48") (pintype "bidirectional"))
      (node (ref "U4") (pin "9") (pinfunction "VDDA/VREF+_9") (pintype "bidirectional"))
    )
    (net (code "2") (name "+5V") (class "Default")
      (node (ref "C2") (pin "1") (pinfunction "1_1") (pintype "passive"))
      (node (ref "C3") (pin "1") (pinfunction "1_1") (pintype "passive"))
      (node (ref "C5") (pin "2") (pinfunction "2_2") (pintype "passive"))
      (node (ref "C6") (pin "1") (pinfunction "1_1") (pintype "passive"))
      (node (ref "FB2") (pin "2") (pinfunction "2_2") (pintype "passive"))
      (node (ref "R3") (pin "2") (pinfunction "2_2") (pintype "passive"))
      (node (ref "R4") (pin "1") (pinfunction "1_1") (pintype "passive"))
      (node (ref "R5") (pin "1") (pinfunction "1_1") (pintype "passive"))
      (node (ref "U1") (pin "1") (pinfunction "VINA_1") (pintype "bidirectional"))
      (node (ref "U1") (pin "10") (pinfunction "VINB_10") (pintype "bidirectional"))
      (node (ref "U1") (pin "14") (pinfunction "CTL3A_14") (pintype "bidirectional"))
      (node (ref "U1") (pin "15") (pinfunction "CTL2A_15") (pintype "bidirectional"))
      (node (ref "U1") (pin "16") (pinfunction "CTL1A_16") (pintype "bidirectional"))
      (node (ref "U1") (pin "17") (pinfunction "CTL0A_17") (pintype "bidirectional"))
      (node (ref "U1") (pin "5") (pinfunction "CTL3B_5") (pintype "bidirectional"))
      (node (ref "U1") (pin "8") (pinfunction "CTL0B_8") (pintype "bidirectional"))
      (node (ref "U2") (pin "2") (pinfunction "VIN_2") (pintype "bidirectional"))
      (node (ref "U4") (pin "30") (pinfunction "PA9_30") (pintype "bidirectional"))
    )
    (net (code "3") (name "133M_OUT_EN") (class "Default")
      (node (ref "R10") (pin "2") (pinfunction "2_2") (pintype "passive"))
      (node (ref "U4") (pin "20") (pinfunction "PB2_20") (pintype "bidirectional"))
      (node (ref "X3") (pin "1") (pinfunction "SBY_1") (pintype "bidirectional"))
    )
    (net (code "4") (name "BOOT0") (class "Default")
      (node (ref "R8") (pin "2") (pinfunction "2_2") (pintype "passive"))
      (node (ref "S1") (pin "P$2") (pinfunction "2_P$2") (pintype "bidirectional"))
      (node (ref "U4") (pin "44") (pinfunction "BOOT0_44") (pintype "bidirectional"))
    )
    (net (code "5") (name "CLKHS") (class "Default")
      (node (ref "R15") (pin "2") (pinfunction "2_2") (pintype "passive"))
      (node (ref "U5") (pin "53") (pinfunction "CLKHS_53") (pintype "bidirectional"))
    )
    (net (code "6") (name "CLKI") (class "Default")
      (node (ref "R18") (pin "2") (pinfunction "2_2") (pintype "passive"))
      (node (ref "U6") (pin "11") (pinfunction "CLK_IN_11") (pintype "bidirectional"))
    )
    (net (code "7") (name "CLKO_B") (class "Default")
      (node (ref "R19") (pin "2") (pinfunction "2_2") (pintype "passive"))
      (node (ref "R22") (pin "1") (pinfunction "1_1") (pintype "passive"))
      (node (ref "U7") (pin "10") (pinfunction "CLK_OUT_10") (pintype "bidirectional"))
    )
    (net (code "8") (name "CLKO_B_32M") (class "Default")
      (node (ref "R22") (pin "2") (pinfunction "2_2") (pintype "passive"))
      (node (ref "U4") (pin "5") (pinfunction "PH0-OSC_IN_5") (pintype "bidirectional"))
    )
    (net (code "9") (name "FEM_EN") (class "Default")
      (node (ref "C22") (pin "1") (pinfunction "1_1") (pintype "passive"))
      (node (ref "IC1") (pin "5") (pinfunction "EN_5") (pintype "bidirectional"))
      (node (ref "R11") (pin "1") (pinfunction "1_1") (pintype "passive"))
      (node (ref "U10") (pin "1") (pinfunction "CSD_1") (pintype "bidirectional"))
    )
    (net (code "10") (name "GND") (class "Default")
      (node (ref "C1") (pin "2") (pinfunction "2_2") (pintype "passive"))
      (node (ref "C10") (pin "2") (pinfunction "2_2") (pintype "passive"))
      (node (ref "C11") (pin "2") (pinfunction "2_2") (pintype "passive"))
      (node (ref "C12") (pin "2") (pinfunction "2_2") (pintype "passive"))
      (node (ref "C13") (pin "2") (pinfunction "2_2") (pintype "passive"))
      (node (ref "C14") (pin "2") (pinfunction "2_2") (pintype "passive"))
      (node (ref "C15") (pin "2") (pinfunction "2_2") (pintype "passive"))
      (node (ref "C16") (pin "2") (pinfunction "2_2") (pintype "passive"))
      (node (ref "C17") (pin "2") (pinfunction "2_2") (pintype "passive"))
      (node (ref "C18") (pin "2") (pinfunction "2_2") (pintype "passive"))
      (node (ref "C19") (pin "2") (pinfunction "2_2") (pintype "passive"))
      (node (ref "C2") (pin "2") (pinfunction "2_2") (pintype "passive"))
      (node (ref "C20") (pin "2") (pinfunction "2_2") (pintype "passive"))
      (node (ref "C21") (pin "2") (pinfunction "2_2") (pintype "passive"))
      (node (ref "C22") (pin "2") (pinfunction "2_2") (pintype "passive"))
      (node (ref "C23") (pin "2") (pinfunction "2_2") (pintype "passive"))
      (node (ref "C24") (pin "2") (pinfunction "2_2") (pintype "passive"))
      (node (ref "C25") (pin "2") (pinfunction "2_2") (pintype "passive"))
      (node (ref "C26") (pin "2") (pinfunction "2_2") (pintype "passive"))
      (node (ref "C27") (pin "2") (pinfunction "2_2") (pintype "passive"))
      (node (ref "C28") (pin "2") (pinfunction "2_2") (pintype "passive"))
      (node (ref "C29") (pin "2") (pinfunction "2_2") (pintype "passive"))
      (node (ref "C3") (pin "2") (pinfunction "2_2") (pintype "passive"))
      (node (ref "C30") (pin "2") (pinfunction "2_2") (pintype "passive"))
      (node (ref "C31") (pin "2") (pinfunction "2_2") (pintype "passive"))
      (node (ref "C32") (pin "2") (pinfunction "2_2") (pintype "passive"))
      (node (ref "C33") (pin "2") (pinfunction "2_2") (pintype "passive"))
      (node (ref "C34") (pin "2") (pinfunction "2_2") (pintype "passive"))
      (node (ref "C35") (pin "2") (pinfunction "2_2") (pintype "passive"))
      (node (ref "C36") (pin "2") (pinfunction "2_2") (pintype "passive"))
      (node (ref "C37") (pin "2") (pinfunction "2_2") (pintype "passive"))
      (node (ref "C38") (pin "2") (pinfunction "2_2") (pintype "passive"))
      (node (ref "C39") (pin "2") (pinfunction "2_2") (pintype "passive"))
      (node (ref "C4") (pin "2") (pinfunction "2_2") (pintype "passive"))
      (node (ref "C41") (pin "1") (pinfunction "1_1") (pintype "passive"))
      (node (ref "C42") (pin "1") (pinfunction "1_1") (pintype "passive"))
      (node (ref "C43") (pin "1") (pinfunction "1_1") (pintype "passive"))
      (node (ref "C44") (pin "2") (pinfunction "2_2") (pintype "passive"))
      (node (ref "C45") (pin "2") (pinfunction "2_2") (pintype "passive"))
      (node (ref "C46") (pin "2") (pinfunction "2_2") (pintype "passive"))
      (node (ref "C47") (pin "2") (pinfunction "2_2") (pintype "passive"))
      (node (ref "C49") (pin "1") (pinfunction "1_1") (pintype "passive"))
      (node (ref "C5") (pin "1") (pinfunction "1_1") (pintype "passive"))
      (node (ref "C50") (pin "1") (pinfunction "1_1") (pintype "passive"))
      (node (ref "C51") (pin "1") (pinfunction "1_1") (pintype "passive"))
      (node (ref "C52") (pin "2") (pinfunction "2_2") (pintype "passive"))
      (node (ref "C53") (pin "2") (pinfunction "2_2") (pintype "passive"))
      (node (ref "C54") (pin "2") (pinfunction "2_2") (pintype "passive"))
      (node (ref "C57") (pin "2") (pinfunction "2_2") (pintype "passive"))
      (node (ref "C58") (pin "2") (pinfunction "2_2") (pintype "passive"))
      (node (ref "C6") (pin "2") (pinfunction "2_2") (pintype "passive"))
      (node (ref "C60") (pin "2") (pinfunction "2_2") (pintype "passive"))
      (node (ref "C62") (pin "2") (pinfunction "2_2") (pintype "passive"))
      (node (ref "C63") (pin "2") (pinfunction "2_2") (pintype "passive"))
      (node (ref "C64") (pin "2") (pinfunction "2_2") (pintype "passive"))
      (node (ref "C65") (pin "2") (pinfunction "2_2") (pintype "passive"))
      (node (ref "C66") (pin "2") (pinfunction "2_2") (pintype "passive"))
      (node (ref "C67") (pin "2") (pinfunction "2_2") (pintype "passive"))
      (node (ref "C69") (pin "2") (pinfunction "2_2") (pintype "passive"))
      (node (ref "C7") (pin "2") (pinfunction "2_2") (pintype "passive"))
      (node (ref "C70") (pin "2") (pinfunction "2_2") (pintype "passive"))
      (node (ref "C71") (pin "2") (pinfunction "2_2") (pintype "passive"))
      (node (ref "C72") (pin "2") (pinfunction "2_2") (pintype "passive"))
      (node (ref "C74") (pin "2") (pinfunction "2_2") (pintype "passive"))
      (node (ref "C75") (pin "2") (pinfunction "2_2") (pintype "passive"))
      (node (ref "C8") (pin "2") (pinfunction "2_2") (pintype "passive"))
      (node (ref "C9") (pin "2") (pinfunction "2_2") (pintype "passive"))
      (node (ref "D1") (pin "2") (pinfunction "2_2") (pintype "bidirectional"))
      (node (ref "D2") (pin "2") (pinfunction "2_2") (pintype "bidirectional"))
      (node (ref "D3") (pin "2") (pinfunction "2_2") (pintype "bidirectional"))
      (node (ref "D4") (pin "2") (pinfunction "2_2") (pintype "bidirectional"))
      (node (ref "D7") (pin "2") (pinfunction "2_2") (pintype "bidirectional"))
      (node (ref "FB1") (pin "1") (pinfunction "1_1") (pintype "passive"))
      (node (ref "FB3") (pin "2") (pinfunction "2_2") (pintype "passive"))
      (node (ref "IC1") (pin "4") (pinfunction "GND_4") (pintype "bidirectional"))
      (node (ref "IC1") (pin "EXP") (pinfunction "GND_EXP") (pintype "bidirectional"))
      (node (ref "JP1") (pin "6") (pinfunction "6_6") (pintype "passive"))
      (node (ref "L3") (pin "2") (pinfunction "2_2") (pintype "passive"))
      (node (ref "P1") (pin "C") (pinfunction "C_C") (pintype "passive"))
      (node (ref "P2") (pin "2") (pinfunction "C_2") (pintype "passive"))
      (node (ref "P3") (pin "2") (pinfunction "C_2") (pintype "passive"))
      (node (ref "R10") (pin "1") (pinfunction "1_1") (pintype "passive"))
      (node (ref "R12") (pin "1") (pinfunction "1_1") (pintype "passive"))
      (node (ref "R21") (pin "1") (pinfunction "1_1") (pintype "bidirectional"))
      (node (ref "R21") (pin "2") (pinfunction "2_2") (pintype "bidirectional"))
      (node (ref "R21") (pin "7") (pinfunction "7_7") (pintype "bidirectional"))
      (node (ref "R21") (pin "8") (pinfunction "8_8") (pintype "bidirectional"))
      (node (ref "R23") (pin "2") (pinfunction "2_2") (pintype "passive"))
      (node (ref "R25") (pin "2") (pinfunction "2_2") (pintype "passive"))
      (node (ref "R26") (pin "1") (pinfunction "1_1") (pintype "passive"))
      (node (ref "R27") (pin "1") (pinfunction "1_1") (pintype "passive"))
      (node (ref "R8") (pin "1") (pinfunction "1_1") (pintype "passive"))
      (node (ref "S2") (pin "P$1") (pinfunction "1_P$1") (pintype "bidirectional"))
      (node (ref "U1") (pin "12") (pinfunction "GNDB_12") (pintype "bidirectional"))
      (node (ref "U1") (pin "13") (pinfunction "GNDA_13") (pintype "bidirectional"))
      (node (ref "U1") (pin "3") (pinfunction "GNDA_3") (pintype "bidirectional"))
      (node (ref "U1") (pin "4") (pinfunction "GNDB_4") (pintype "bidirectional"))
      (node (ref "U1") (pin "6") (pinfunction "CTL2B_6") (pintype "bidirectional"))
      (node (ref "U1") (pin "7") (pinfunction "CTL1B_7") (pintype "bidirectional"))
      (node (ref "U1") (pin "T1") (pinfunction "GNDA_T1") (pintype "bidirectional"))
      (node (ref "U1") (pin "T2") (pinfunction "GNDB_T2") (pintype "bidirectional"))
      (node (ref "U10") (pin "10") (pinfunction "N/C_10") (pintype "bidirectional"))
      (node (ref "U10") (pin "13") (pinfunction "N/C_13") (pintype "bidirectional"))
      (node (ref "U10") (pin "15") (pinfunction "N/C_15") (pintype "bidirectional"))
      (node (ref "U10") (pin "17") (pinfunction "N/C_17") (pintype "bidirectional"))
      (node (ref "U10") (pin "18") (pinfunction "N/C_18") (pintype "bidirectional"))
      (node (ref "U10") (pin "7") (pinfunction "ANT_SEL_7") (pintype "bidirectional"))
      (node (ref "U10") (pin "8") (pinfunction "GND_8") (pintype "bidirectional"))
      (node (ref "U10") (pin "GND") (pinfunction "GND_GND") (pintype "bidirectional"))
      (node (ref "U11") (pin "1") (pinfunction "GND_1") (pintype "bidirectional"))
      (node (ref "U11") (pin "3") (pinfunction "GND_3") (pintype "bidirectional"))
      (node (ref "U11") (pin "4") (pinfunction "GND_4") (pintype "bidirectional"))
      (node (ref "U11") (pin "6") (pinfunction "GND_6") (pintype "bidirectional"))
      (node (ref "U2") (pin "5") (pinfunction "GND_5") (pintype "bidirectional"))
      (node (ref "U4") (pin "23") (pinfunction "VSS_23") (pintype "bidirectional"))
      (node (ref "U4") (pin "35") (pinfunction "VSS_35") (pintype "bidirectional"))
      (node (ref "U4") (pin "47") (pinfunction "VSS_47") (pintype "bidirectional"))
      (node (ref "U4") (pin "8") (pinfunction "VSSA/VREF-_8") (pintype "bidirectional"))
      (node (ref "U4") (pin "EXP") (pinfunction "VSS_EXP") (pintype "bidirectional"))
      (node (ref "U5") (pin "10") (pinfunction "VSS_10") (pintype "bidirectional"))
      (node (ref "U5") (pin "11") (pinfunction "VSS_11") (pintype "bidirectional"))
      (node (ref "U5") (pin "16") (pinfunction "NC_16") (pintype "bidirectional"))
      (node (ref "U5") (pin "24") (pinfunction "VSS_24") (pintype "bidirectional"))
      (node (ref "U5") (pin "30") (pinfunction "VSS_30") (pintype "bidirectional"))
      (node (ref "U5") (pin "31") (pinfunction "VSS_31") (pintype "bidirectional"))
      (node (ref "U5") (pin "32") (pinfunction "NC_32") (pintype "bidirectional"))
      (node (ref "U5") (pin "33") (pinfunction "NC_33") (pintype "bidirectional"))
      (node (ref "U5") (pin "34") (pinfunction "SP_VALID_34") (pintype "bidirectional"))
      (node (ref "U5") (pin "40") (pinfunction "GND_40") (pintype "bidirectional"))
      (node (ref "U5") (pin "41") (pinfunction "GND_41") (pintype "bidirectional"))
      (node (ref "U5") (pin "48") (pinfunction "NC_48") (pintype "bidirectional"))
      (node (ref "U5") (pin "49") (pinfunction "NC_49") (pintype "bidirectional"))
      (node (ref "U5") (pin "50") (pinfunction "VSS_50") (pintype "bidirectional"))
      (node (ref "U5") (pin "51") (pinfunction "VSS_51") (pintype "bidirectional"))
      (node (ref "U5") (pin "59") (pinfunction "VSS_59") (pintype "bidirectional"))
      (node (ref "U5") (pin "6") (pinfunction "SCANMODE_6") (pintype "bidirectional"))
      (node (ref "U5") (pin "7") (pinfunction "VSS_7") (pintype "bidirectional"))
      (node (ref "U5") (pin "EXP") (pinfunction "VSS_EXP") (pintype "bidirectional"))
      (node (ref "U6") (pin "26") (pinfunction "GND_26") (pintype "bidirectional"))
      (node (ref "U6") (pin "28") (pinfunction "GND_28") (pintype "bidirectional"))
      (node (ref "U6") (pin "31") (pinfunction "GND_31") (pintype "bidirectional"))
      (node (ref "U6") (pin "4") (pinfunction "GND_4") (pintype "bidirectional"))
      (node (ref "U6") (pin "7") (pinfunction "GND_7") (pintype "bidirectional"))
      (node (ref "U6") (pin "EXP") (pinfunction "GND_EXP") (pintype "bidirectional"))
      (node (ref "U7") (pin "12") (pinfunction "Q_IN_12") (pintype "bidirectional"))
      (node (ref "U7") (pin "13") (pinfunction "I_IN_13") (pintype "bidirectional"))
      (node (ref "U7") (pin "26") (pinfunction "GND_26") (pintype "bidirectional"))
      (node (ref "U7") (pin "28") (pinfunction "GND_28") (pintype "bidirectional"))
      (node (ref "U7") (pin "31") (pinfunction "GND_31") (pintype "bidirectional"))
      (node (ref "U7") (pin "4") (pinfunction "GND_4") (pintype "bidirectional"))
      (node (ref "U7") (pin "7") (pinfunction "GND_7") (pintype "bidirectional"))
      (node (ref "U7") (pin "EXP") (pinfunction "GND_EXP") (pintype "bidirectional"))
      (node (ref "U8") (pin "1") (pinfunction "GND_1") (pintype "bidirectional"))
      (node (ref "U8") (pin "3") (pinfunction "GND_3") (pintype "bidirectional"))
      (node (ref "U8") (pin "4") (pinfunction "GND_4") (pintype "bidirectional"))
      (node (ref "U8") (pin "6") (pinfunction "GND_6") (pintype "bidirectional"))
      (node (ref "U9") (pin "1") (pinfunction "GND_1") (pintype "bidirectional"))
      (node (ref "U9") (pin "3") (pinfunction "GND_3") (pintype "bidirectional"))
      (node (ref "U9") (pin "4") (pinfunction "GND_4") (pintype "bidirectional"))
      (node (ref "U9") (pin "6") (pinfunction "GND_6") (pintype "bidirectional"))
      (node (ref "X2") (pin "3") (pinfunction "S_3") (pintype "passive"))
      (node (ref "X3") (pin "2") (pinfunction "GND_2") (pintype "bidirectional"))
      (node (ref "X4") (pin "1") (pinfunction "GND_1") (pintype "bidirectional"))
      (node (ref "X4") (pin "2") (pinfunction "GND_2") (pintype "bidirectional"))
      (node (ref "X5") (pin "G@1") (pinfunction "GND_G@1") (pintype "bidirectional"))
      (node (ref "X5") (pin "G@2") (pinfunction "GND_G@2") (pintype "bidirectional"))
      (node (ref "X5") (pin "G@3") (pinfunction "GND_G@3") (pintype "bidirectional"))
      (node (ref "X5") (pin "G@4") (pinfunction "GND_G@4") (pintype "bidirectional"))
    )
    (net (code "11") (name "GPIO0") (class "Default")
      (node (ref "U4") (pin "19") (pinfunction "PB1_19") (pintype "bidirectional"))
      (node (ref "U5") (pin "58") (pinfunction "GPIO[0]_58") (pintype "bidirectional"))
    )
    (net (code "12") (name "GPIO2") (class "Default")
      (node (ref "U4") (pin "12") (pinfunction "PA2_12") (pintype "bidirectional"))
      (node (ref "U5") (pin "56") (pinfunction "GPIO[2]_56") (pintype "bidirectional"))
    )
    (net (code "13") (name "GPIO3") (class "Default")
      (node (ref "U4") (pin "29") (pinfunction "PA8_29") (pintype "bidirectional"))
      (node (ref "U5") (pin "55") (pinfunction "GPIO[3]_55") (pintype "bidirectional"))
    )
    (net (code "14") (name "I2C1_SCL") (class "Default")
      (node (ref "U4") (pin "43") (pinfunction "PB7_43") (pintype "bidirectional"))
    )
    (net (code "15") (name "I2C1_SDA") (class "Default")
      (node (ref "U4") (pin "42") (pinfunction "PB6_42") (pintype "bidirectional"))
    )
    (net (code "16") (name "IRXD_A") (class "Default")
      (node (ref "R20") (pin "5") (pinfunction "5_5") (pintype "bidirectional"))
      (node (ref "U6") (pin "15") (pinfunction "I_OUT_15") (pintype "bidirectional"))
    )
    (net (code "17") (name "IRXD_B") (class "Default")
      (node (ref "R21") (pin "5") (pinfunction "5_5") (pintype "bidirectional"))
      (node (ref "U7") (pin "15") (pinfunction "I_OUT_15") (pintype "bidirectional"))
    )
    (net (code "18") (name "ITXD_A") (class "Default")
      (node (ref "R20") (pin "7") (pinfunction "7_7") (pintype "bidirectional"))
      (node (ref "U6") (pin "13") (pinfunction "I_IN_13") (pintype "bidirectional"))
    )
    (net (code "19") (name "LNA_EN") (class "Default")
      (node (ref "C28") (pin "1") (pinfunction "1_1") (pintype "passive"))
      (node (ref "R13") (pin "1") (pinfunction "1_1") (pintype "passive"))
      (node (ref "U10") (pin "3") (pinfunction "CPS_3") (pintype "bidirectional"))
    )
    (net (code "20") (name "MISO_A") (class "Default")
      (node (ref "U5") (pin "62") (pinfunction "RADIO_A_MISO_62") (pintype "bidirectional"))
      (node (ref "U6") (pin "18") (pinfunction "MISO_18") (pintype "bidirectional"))
    )
    (net (code "21") (name "MISO_B") (class "Default")
      (node (ref "U5") (pin "21") (pinfunction "RADIO_B_MISO_21") (pintype "bidirectional"))
      (node (ref "U7") (pin "18") (pinfunction "MISO_18") (pintype "bidirectional"))
    )
    (net (code "22") (name "MOSI_A") (class "Default")
      (node (ref "U5") (pin "63") (pinfunction "RADIO_A_MOSI_63") (pintype "bidirectional"))
      (node (ref "U6") (pin "19") (pinfunction "MOSI_19") (pintype "bidirectional"))
    )
    (net (code "23") (name "MOSI_B") (class "Default")
      (node (ref "U5") (pin "20") (pinfunction "RADIO_B_MOSI_20") (pintype "bidirectional"))
      (node (ref "U7") (pin "19") (pinfunction "MOSI_19") (pintype "bidirectional"))
    )
    (net (code "24") (name "NRST") (class "Default")
      (node (ref "C13") (pin "1") (pinfunction "1_1") (pintype "passive"))
      (node (ref "R9") (pin "1") (pinfunction "1_1") (pintype "passive"))
      (node (ref "S2") (pin "P$2") (pinfunction "2_P$2") (pintype "bidirectional"))
      (node (ref "U4") (pin "7") (pinfunction "NRST_7") (pintype "bidirectional"))
      (node (ref "X2") (pin "1") (pinfunction "S_1") (pintype "passive"))
    )
    (net (code "25") (name "NSS_A") (class "Default")
      (node (ref "U5") (pin "64") (pinfunction "RADIO_A_CS_64") (pintype "bidirectional"))
      (node (ref "U6") (pin "20") (pinfunction "NSS_20") (pintype "bidirectional"))
    )
    (net (code "26") (name "NSS_B") (class "Default")
      (node (ref "U5") (pin "19") (pinfunction "RADIO_B_CS_19") (pintype "bidirectional"))
      (node (ref "U7") (pin "20") (pinfunction "NSS_20") (pintype "bidirectional"))
    )
    (net (code "27") (name "Net-(C7-Pad1)") (class "Default")
      (node (ref "C7") (pin "1") (pinfunction "1_1") (pintype "passive"))
      (node (ref "FB4") (pin "2") (pinfunction "2_2") (pintype "passive"))
      (node (ref "IC1") (pin "7") (pinfunction "VIN_7") (pintype "bidirectional"))
      (node (ref "IC1") (pin "8") (pinfunction "VIN_8") (pintype "bidirectional"))
    )
    (net (code "28") (name "Net-(C31-Pad1)") (class "Default")
      (node (ref "C31") (pin "1") (pinfunction "1_1") (pintype "passive"))
      (node (ref "U5") (pin "23") (pinfunction "VCC18_23") (pintype "bidirectional"))
    )
    (net (code "29") (name "Net-(C33-Pad1)") (class "Default")
      (node (ref "C33") (pin "1") (pinfunction "1_1") (pintype "passive"))
      (node (ref "C34") (pin "1") (pinfunction "1_1") (pintype "passive"))
      (node (ref "U5") (pin "52") (pinfunction "VCC33_52") (pintype "bidirectional"))
    )
    (net (code "30") (name "Net-(C56-Pad1)") (class "Default")
      (node (ref "C56") (pin "1") (pinfunction "1_1") (pintype "passive"))
      (node (ref "L4") (pin "1") (pinfunction "1_1") (pintype "passive"))
    )
    (net (code "31") (name "Net-(C59-Pad2)") (class "Default")
      (node (ref "C59") (pin "2") (pinfunction "2_2") (pintype "passive"))
      (node (ref "R24") (pin "1") (pinfunction "1_1") (pintype "passive"))
      (node (ref "R25") (pin "1") (pinfunction "1_1") (pintype "passive"))
    )
    (net (code "32") (name "Net-(C67-Pad1)") (class "Default")
      (node (ref "C67") (pin "1") (pinfunction "1_1") (pintype "passive"))
      (node (ref "C70") (pin "1") (pinfunction "1_1") (pintype "passive"))
      (node (ref "L11") (pin "2") (pinfunction "2_2") (pintype "passive"))
      (node (ref "L8") (pin "1") (pinfunction "1_1") (pintype "passive"))
    )
    (net (code "33") (name "Net-(C68-Pad2)") (class "Default")
      (node (ref "C68") (pin "2") (pinfunction "2_2") (pintype "passive"))
      (node (ref "C69") (pin "1") (pinfunction "1_1") (pintype "passive"))
      (node (ref "L10") (pin "2") (pinfunction "2_2") (pintype "passive"))
      (node (ref "L9") (pin "1") (pinfunction "1_1") (pintype "passive"))
    )
    (net (code "34") (name "Net-(C71-Pad1)") (class "Default")
      (node (ref "C71") (pin "1") (pinfunction "1_1") (pintype "passive"))
      (node (ref "C73") (pin "1") (pinfunction "1_1") (pintype "passive"))
      (node (ref "D7") (pin "1") (pinfunction "1_1") (pintype "bidirectional"))
      (node (ref "L10") (pin "1") (pinfunction "1_1") (pintype "passive"))
    )
    (net (code "35") (name "Net-(C73-Pad2)") (class "Default")
      (node (ref "C73") (pin "2") (pinfunction "2_2") (pintype "passive"))
      (node (ref "X5") (pin "1") (pinfunction "1_1") (pintype "bidirectional"))
    )
    (net (code "36") (name "Net-(FB1-Pad2)") (class "Default")
      (node (ref "FB1") (pin "2") (pinfunction "2_2") (pintype "passive"))
      (node (ref "X1") (pin "6") (pinfunction "SHIELD_6") (pintype "bidirectional"))
      (node (ref "X1") (pin "7") (pinfunction "SHIELD_7") (pintype "bidirectional"))
      (node (ref "X1") (pin "8") (pinfunction "SHIELD_8") (pintype "bidirectional"))
      (node (ref "X1") (pin "9") (pinfunction "SHIELD_9") (pintype "bidirectional"))
    )
    (net (code "37") (name "Net-(IC1-NR)") (class "Default")
      (node (ref "C75") (pin "1") (pinfunction "1_1") (pintype "passive"))
      (node (ref "IC1") (pin "6") (pinfunction "NR_6") (pintype "bidirectional"))
    )
    (net (code "38") (name "Net-(P1-PadA)") (class "Default")
      (node (ref "P1") (pin "A") (pinfunction "A_A") (pintype "passive"))
      (node (ref "R3") (pin "1") (pinfunction "1_1") (pintype "passive"))
    )
    (net (code "39") (name "Net-(P2-A)") (class "Default")
      (node (ref "P2") (pin "1") (pinfunction "A_1") (pintype "passive"))
      (node (ref "R16") (pin "2") (pinfunction "2_2") (pintype "passive"))
    )
    (net (code "40") (name "Net-(P3-A)") (class "Default")
      (node (ref "P3") (pin "1") (pinfunction "A_1") (pintype "passive"))
      (node (ref "R17") (pin "2") (pinfunction "2_2") (pintype "passive"))
    )
    (net (code "41") (name "Net-(U1-LXA)") (class "Default")
      (node (ref "L1") (pin "1") (pinfunction "1_1") (pintype "passive"))
      (node (ref "U1") (pin "2") (pinfunction "LXA_2") (pintype "bidirectional"))
    )
    (net (code "42") (name "Net-(U1-LXB)") (class "Default")
      (node (ref "L2") (pin "2") (pinfunction "2_2") (pintype "passive"))
      (node (ref "U1") (pin "11") (pinfunction "LXB_11") (pintype "bidirectional"))
    )
    (net (code "43") (name "Net-(U2-BYP)") (class "Default")
      (node (ref "C8") (pin "1") (pinfunction "1_1") (pintype "passive"))
      (node (ref "U2") (pin "7") (pinfunction "BYP_7") (pintype "bidirectional"))
    )
    (net (code "44") (name "Net-(U4-PB0)") (class "Default")
      (node (ref "R11") (pin "2") (pinfunction "2_2") (pintype "passive"))
      (node (ref "U4") (pin "18") (pinfunction "PB0_18") (pintype "bidirectional"))
    )
    (net (code "45") (name "Net-(U4-VCAP1)") (class "Default")
      (node (ref "C14") (pin "1") (pinfunction "1_1") (pintype "passive"))
      (node (ref "U4") (pin "22") (pinfunction "VCAP1_22") (pintype "bidirectional"))
    )
    (net (code "46") (name "Net-(U5-A_IQ_RX)") (class "Default")
      (node (ref "R20") (pin "4") (pinfunction "4_4") (pintype "bidirectional"))
      (node (ref "U5") (pin "44") (pinfunction "A_IQ_RX_44") (pintype "bidirectional"))
    )
    (net (code "47") (name "Net-(U5-A_IQ_TX)") (class "Default")
      (node (ref "R20") (pin "2") (pinfunction "2_2") (pintype "bidirectional"))
      (node (ref "U5") (pin "46") (pinfunction "A_IQ_TX_46") (pintype "bidirectional"))
    )
    (net (code "48") (name "Net-(U5-A_QI_RX)") (class "Default")
      (node (ref "R20") (pin "3") (pinfunction "3_3") (pintype "bidirectional"))
      (node (ref "U5") (pin "45") (pinfunction "A_QI_RX_45") (pintype "bidirectional"))
    )
    (net (code "49") (name "Net-(U5-A_QI_TX)") (class "Default")
      (node (ref "R20") (pin "1") (pinfunction "1_1") (pintype "bidirectional"))
      (node (ref "U5") (pin "47") (pinfunction "A_QI_TX_47") (pintype "bidirectional"))
    )
    (net (code "50") (name "Net-(U5-B_IQ_RX)") (class "Default")
      (node (ref "R21") (pin "4") (pinfunction "4_4") (pintype "bidirectional"))
      (node (ref "U5") (pin "35") (pinfunction "B_IQ_RX_35") (pintype "bidirectional"))
    )
    (net (code "51") (name "Net-(U5-B_QI_RX)") (class "Default")
      (node (ref "R21") (pin "3") (pinfunction "3_3") (pintype "bidirectional"))
      (node (ref "U5") (pin "36") (pinfunction "B_QI_RX_36") (pintype "bidirectional"))
    )
    (net (code "52") (name "Net-(U5-CLK32M)") (class "Default")
      (node (ref "R19") (pin "1") (pinfunction "1_1") (pintype "passive"))
      (node (ref "U5") (pin "43") (pinfunction "CLK32M_43") (pintype "bidirectional"))
    )
    (net (code "53") (name "Net-(U5-LNA_A_CTRL)") (class "Default")
      (node (ref "R13") (pin "2") (pinfunction "2_2") (pintype "passive"))
      (node (ref "U5") (pin "14") (pinfunction "LNA_A_CTRL_14") (pintype "bidirectional"))
    )
    (net (code "54") (name "Net-(U5-PA_A_CTRL)") (class "Default")
      (node (ref "R14") (pin "2") (pinfunction "2_2") (pintype "passive"))
      (node (ref "U5") (pin "15") (pinfunction "PA_A_CTRL_15") (pintype "bidirectional"))
    )
    (net (code "55") (name "Net-(U5-SP_CLK_OUT)") (class "Default")
      (node (ref "R18") (pin "1") (pinfunction "1_1") (pintype "passive"))
      (node (ref "U5") (pin "39") (pinfunction "SP_CLK_OUT_39") (pintype "bidirectional"))
    )
    (net (code "56") (name "Net-(U6-RESET)") (class "Default")
      (node (ref "D5") (pin "C") (pinfunction "C_C") (pintype "passive"))
      (node (ref "U6") (pin "9") (pinfunction "RESET_9") (pintype "bidirectional"))
    )
    (net (code "57") (name "Net-(U6-RF_IN)") (class "Default")
      (node (ref "L3") (pin "1") (pinfunction "1_1") (pintype "passive"))
      (node (ref "L4") (pin "2") (pinfunction "2_2") (pintype "passive"))
      (node (ref "U6") (pin "27") (pinfunction "RF_IN_27") (pintype "bidirectional"))
      (node (ref "U7") (pin "27") (pinfunction "RF_IN_27") (pintype "bidirectional"))
    )
    (net (code "58") (name "Net-(U6-RF_ON)") (class "Default")
      (node (ref "C44") (pin "1") (pinfunction "1_1") (pintype "passive"))
      (node (ref "U6") (pin "29") (pinfunction "RF_ON_29") (pintype "bidirectional"))
    )
    (net (code "59") (name "Net-(U6-RF_OP)") (class "Default")
      (node (ref "C55") (pin "1") (pinfunction "1_1") (pintype "passive"))
      (node (ref "U6") (pin "30") (pinfunction "RF_OP_30") (pintype "bidirectional"))
    )
    (net (code "60") (name "Net-(U6-VR_ANA1)") (class "Default")
      (node (ref "C42") (pin "2") (pinfunction "2_2") (pintype "passive"))
      (node (ref "U6") (pin "3") (pinfunction "VR_ANA1_3") (pintype "bidirectional"))
    )
    (net (code "61") (name "Net-(U6-VR_ANA2)") (class "Default")
      (node (ref "C74") (pin "1") (pinfunction "1_1") (pintype "passive"))
      (node (ref "U6") (pin "25") (pinfunction "VR_ANA2_25") (pintype "bidirectional"))
    )
    (net (code "62") (name "Net-(U6-VR_DIG)") (class "Default")
      (node (ref "C41") (pin "2") (pinfunction "2_2") (pintype "passive"))
      (node (ref "U6") (pin "5") (pinfunction "VR_DIG_5") (pintype "bidirectional"))
    )
    (net (code "63") (name "Net-(U6-VR_PA)") (class "Default")
      (node (ref "C43") (pin "2") (pinfunction "2_2") (pintype "passive"))
      (node (ref "U6") (pin "1") (pinfunction "VR_PA_1") (pintype "bidirectional"))
    )
    (net (code "64") (name "Net-(U6-XTB)") (class "Default")
      (node (ref "C40") (pin "1") (pinfunction "1_1") (pintype "passive"))
      (node (ref "U6") (pin "8") (pinfunction "XTB_8") (pintype "bidirectional"))
    )
    (net (code "65") (name "Net-(U7-RESET)") (class "Default")
      (node (ref "D6") (pin "C") (pinfunction "C_C") (pintype "passive"))
      (node (ref "U7") (pin "9") (pinfunction "RESET_9") (pintype "bidirectional"))
    )
    (net (code "66") (name "Net-(U7-VR_ANA1)") (class "Default")
      (node (ref "C50") (pin "2") (pinfunction "2_2") (pintype "passive"))
      (node (ref "U7") (pin "3") (pinfunction "VR_ANA1_3") (pintype "bidirectional"))
    )
    (net (code "67") (name "Net-(U7-VR_ANA2)") (class "Default")
      (node (ref "C52") (pin "1") (pinfunction "1_1") (pintype "passive"))
      (node (ref "U7") (pin "25") (pinfunction "VR_ANA2_25") (pintype "bidirectional"))
    )
    (net (code "68") (name "Net-(U7-VR_DIG)") (class "Default")
      (node (ref "C49") (pin "2") (pinfunction "2_2") (pintype "passive"))
      (node (ref "U7") (pin "5") (pinfunction "VR_DIG_5") (pintype "bidirectional"))
    )
    (net (code "69") (name "Net-(U7-VR_PA)") (class "Default")
      (node (ref "C51") (pin "2") (pinfunction "2_2") (pintype "passive"))
      (node (ref "U7") (pin "1") (pinfunction "VR_PA_1") (pintype "bidirectional"))
    )
    (net (code "70") (name "Net-(U7-XTB)") (class "Default")
      (node (ref "C48") (pin "1") (pinfunction "1_1") (pintype "passive"))
      (node (ref "U7") (pin "8") (pinfunction "XTB_8") (pintype "bidirectional"))
    )
    (net (code "71") (name "Net-(U8-IN)") (class "Default")
      (node (ref "C55") (pin "2") (pinfunction "2_2") (pintype "passive"))
      (node (ref "U8") (pin "2") (pinfunction "IN_2") (pintype "bidirectional"))
    )
    (net (code "72") (name "Net-(U8-OUT)") (class "Default")
      (node (ref "R23") (pin "1") (pinfunction "1_1") (pintype "passive"))
      (node (ref "R24") (pin "2") (pinfunction "2_2") (pintype "passive"))
      (node (ref "U8") (pin "5") (pinfunction "OUT_5") (pintype "bidirectional"))
    )
    (net (code "73") (name "Net-(U9-IN)") (class "Default")
      (node (ref "C61") (pin "1") (pinfunction "1_1") (pintype "passive"))
      (node (ref "U9") (pin "2") (pinfunction "IN_2") (pintype "bidirectional"))
    )
    (net (code "74") (name "Net-(U9-OUT)") (class "Default")
      (node (ref "C56") (pin "2") (pinfunction "2_2") (pintype "passive"))
      (node (ref "C57") (pin "1") (pinfunction "1_1") (pintype "passive"))
      (node (ref "U9") (pin "5") (pinfunction "OUT_5") (pintype "bidirectional"))
    )
    (net (code "75") (name "Net-(U10-ANT1)") (class "Default")
      (node (ref "C65") (pin "1") (pinfunction "1_1") (pintype "passive"))
      (node (ref "C68") (pin "1") (pinfunction "1_1") (pintype "passive"))
      (node (ref "L9") (pin "2") (pinfunction "2_2") (pintype "passive"))
      (node (ref "U10") (pin "14") (pinfunction "ANT1_14") (pintype "bidirectional"))
    )
    (net (code "76") (name "Net-(U10-ANT2)") (class "Default")
      (node (ref "R27") (pin "2") (pinfunction "2_2") (pintype "passive"))
      (node (ref "U10") (pin "12") (pinfunction "ANT2_12") (pintype "bidirectional"))
    )
    (net (code "77") (name "Net-(U10-LNA_IN)") (class "Default")
      (node (ref "U10") (pin "9") (pinfunction "LNA_IN_9") (pintype "bidirectional"))
      (node (ref "U11") (pin "5") (pinfunction "OUT_5") (pintype "bidirectional"))
    )
    (net (code "78") (name "Net-(U10-PA_IN)") (class "Default")
      (node (ref "C59") (pin "1") (pinfunction "1_1") (pintype "passive"))
      (node (ref "U10") (pin "2") (pinfunction "PA_IN_2") (pintype "bidirectional"))
    )
    (net (code "79") (name "Net-(U10-PA_OUT)") (class "Default")
      (node (ref "L8") (pin "2") (pinfunction "2_2") (pintype "passive"))
      (node (ref "U10") (pin "20") (pinfunction "PA_OUT_20") (pintype "bidirectional"))
    )
    (net (code "80") (name "Net-(U10-RX_FLT)") (class "Default")
      (node (ref "U10") (pin "11") (pinfunction "RX_FLT_11") (pintype "bidirectional"))
      (node (ref "U11") (pin "2") (pinfunction "IN_2") (pintype "bidirectional"))
    )
    (net (code "81") (name "Net-(U10-TR)") (class "Default")
      (node (ref "C61") (pin "2") (pinfunction "2_2") (pintype "passive"))
      (node (ref "U10") (pin "6") (pinfunction "TR_6") (pintype "bidirectional"))
    )
    (net (code "82") (name "Net-(U10-TX_FLT)") (class "Default")
      (node (ref "R26") (pin "2") (pinfunction "2_2") (pintype "passive"))
      (node (ref "U10") (pin "5") (pinfunction "TX_FLT_5") (pintype "bidirectional"))
    )
    (net (code "83") (name "Net-(U10-TX_IN)") (class "Default")
      (node (ref "C72") (pin "1") (pinfunction "1_1") (pintype "passive"))
      (node (ref "L11") (pin "1") (pinfunction "1_1") (pintype "passive"))
      (node (ref "U10") (pin "16") (pinfunction "TX_IN_16") (pintype "bidirectional"))
    )
    (net (code "84") (name "Net-(U10-VCC0)") (class "Default")
      (node (ref "C63") (pin "1") (pinfunction "1_1") (pintype "passive"))
      (node (ref "L6") (pin "1") (pinfunction "1_1") (pintype "passive"))
      (node (ref "U10") (pin "23") (pinfunction "VCC0_23") (pintype "bidirectional"))
    )
    (net (code "85") (name "Net-(U10-VCC1)") (class "Default")
      (node (ref "C62") (pin "1") (pinfunction "1_1") (pintype "passive"))
      (node (ref "L5") (pin "1") (pinfunction "1_1") (pintype "passive"))
      (node (ref "U10") (pin "24") (pinfunction "VCC1_24") (pintype "bidirectional"))
    )
    (net (code "86") (name "Net-(U10-VCC2)") (class "Default")
      (node (ref "L7") (pin "2") (pinfunction "2_2") (pintype "passive"))
      (node (ref "U10") (pin "21") (pinfunction "VCC2_21") (pintype "bidirectional"))
    )
    (net (code "87") (name "Net-(X1-D+)") (class "Default")
      (node (ref "D4") (pin "1") (pinfunction "1_1") (pintype "bidirectional"))
      (node (ref "R2") (pin "1") (pinfunction "1_1") (pintype "passive"))
      (node (ref "X1") (pin "3") (pinfunction "D+_3") (pintype "bidirectional"))
    )
    (net (code "88") (name "Net-(X1-D-)") (class "Default")
      (node (ref "D3") (pin "1") (pinfunction "1_1") (pintype "bidirectional"))
      (node (ref "R1") (pin "1") (pinfunction "1_1") (pintype "passive"))
      (node (ref "X1") (pin "2") (pinfunction "D-_2") (pintype "bidirectional"))
    )
    (net (code "89") (name "Net-(X1-GND)") (class "Default")
      (node (ref "D1") (pin "1") (pinfunction "1_1") (pintype "bidirectional"))
      (node (ref "FB3") (pin "1") (pinfunction "1_1") (pintype "passive"))
      (node (ref "X1") (pin "5") (pinfunction "GND_5") (pintype "power_in"))
    )
    (net (code "90") (name "Net-(X1-VCC)") (class "Default")
      (node (ref "D2") (pin "1") (pinfunction "1_1") (pintype "bidirectional"))
      (node (ref "FB2") (pin "1") (pinfunction "1_1") (pintype "passive"))
      (node (ref "X1") (pin "1") (pinfunction "VCC_1") (pintype "bidirectional"))
    )
    (net (code "91") (name "Net-(X2E-S)") (class "Default")
      (node (ref "C12") (pin "1") (pinfunction "1_1") (pintype "passive"))
      (node (ref "FB5") (pin "1") (pinfunction "1_1") (pintype "passive"))
      (node (ref "X2") (pin "5") (pinfunction "S_5") (pintype "passive"))
    )
    (net (code "92") (name "Net-(X3-OUT)") (class "Default")
      (node (ref "R15") (pin "1") (pinfunction "1_1") (pintype "passive"))
      (node (ref "X3") (pin "3") (pinfunction "OUT_3") (pintype "bidirectional"))
    )
    (net (code "93") (name "Net-(X3-VCC)") (class "Default")
      (node (ref "C24") (pin "1") (pinfunction "1_1") (pintype "passive"))
      (node (ref "FB7") (pin "2") (pinfunction "2_2") (pintype "passive"))
      (node (ref "X3") (pin "4") (pinfunction "VCC_4") (pintype "bidirectional"))
    )
    (net (code "94") (name "Net-(X4-VCC)") (class "Default")
      (node (ref "C39") (pin "1") (pinfunction "1_1") (pintype "passive"))
      (node (ref "FB9") (pin "2") (pinfunction "2_2") (pintype "passive"))
      (node (ref "X4") (pin "4") (pinfunction "VCC_4") (pintype "bidirectional"))
    )
    (net (code "95") (name "PA_EN") (class "Default")
      (node (ref "C29") (pin "1") (pinfunction "1_1") (pintype "passive"))
      (node (ref "R14") (pin "1") (pinfunction "1_1") (pintype "passive"))
      (node (ref "U10") (pin "4") (pinfunction "CTX_4") (pintype "bidirectional"))
    )
    (net (code "96") (name "PPS") (class "Default")
      (node (ref "U4") (pin "21") (pinfunction "PB10_21") (pintype "bidirectional"))
      (node (ref "U5") (pin "9") (pinfunction "GPS_IN_9") (pintype "bidirectional"))
    )
    (net (code "97") (name "QRXD_A") (class "Default")
      (node (ref "R20") (pin "6") (pinfunction "6_6") (pintype "bidirectional"))
      (node (ref "U6") (pin "14") (pinfunction "Q_OUT_14") (pintype "bidirectional"))
    )
    (net (code "98") (name "QRXD_B") (class "Default")
      (node (ref "R21") (pin "6") (pinfunction "6_6") (pintype "bidirectional"))
      (node (ref "U7") (pin "14") (pinfunction "Q_OUT_14") (pintype "bidirectional"))
    )
    (net (code "99") (name "QTXD_A") (class "Default")
      (node (ref "R20") (pin "8") (pinfunction "8_8") (pintype "bidirectional"))
      (node (ref "U6") (pin "12") (pinfunction "Q_IN_12") (pintype "bidirectional"))
    )
    (net (code "100") (name "RADIO2_RST") (class "Default")
      (node (ref "U4") (pin "31") (pinfunction "PA10_31") (pintype "bidirectional"))
    )
    (net (code "101") (name "RADIO_EN_A") (class "Default")
      (node (ref "R4") (pin "2") (pinfunction "2_2") (pintype "passive"))
      (node (ref "U2") (pin "6") (pinfunction "ENA_6") (pintype "bidirectional"))
      (node (ref "U4") (pin "45") (pinfunction "PB8_45") (pintype "bidirectional"))
    )
    (net (code "102") (name "RADIO_EN_B") (class "Default")
      (node (ref "R5") (pin "2") (pinfunction "2_2") (pintype "passive"))
      (node (ref "U2") (pin "4") (pinfunction "ENB_4") (pintype "bidirectional"))
      (node (ref "U4") (pin "46") (pinfunction "PB9_46") (pintype "bidirectional"))
    )
    (net (code "103") (name "RADIO_RST") (class "Default")
      (node (ref "D5") (pin "A") (pinfunction "A_A") (pintype "passive"))
      (node (ref "D6") (pin "A") (pinfunction "A_A") (pintype "passive"))
      (node (ref "U4") (pin "10") (pinfunction "PA0_10") (pintype "bidirectional"))
    )
    (net (code "104") (name "RESET") (class "Default")
      (node (ref "JP1") (pin "1") (pinfunction "1_1") (pintype "passive"))
      (node (ref "R12") (pin "2") (pinfunction "2_2") (pintype "passive"))
      (node (ref "U4") (pin "13") (pinfunction "PA3_13") (pintype "bidirectional"))
      (node (ref "U5") (pin "1") (pinfunction "RESET_1") (pintype "bidirectional"))
    )
    (net (code "105") (name "RX_ON") (class "Default")
      (node (ref "R17") (pin "1") (pinfunction "1_1") (pintype "passive"))
      (node (ref "U4") (pin "41") (pinfunction "PB5_41") (pintype "bidirectional"))
      (node (ref "U5") (pin "57") (pinfunction "GPIO[1]_57") (pintype "bidirectional"))
    )
    (net (code "106") (name "SCK_A") (class "Default")
      (node (ref "U5") (pin "61") (pinfunction "RADIO_A_SCK_61") (pintype "bidirectional"))
      (node (ref "U6") (pin "17") (pinfunction "SCK_17") (pintype "bidirectional"))
    )
    (net (code "107") (name "SCK_B") (class "Default")
      (node (ref "U5") (pin "22") (pinfunction "RADIO_B_SCK_22") (pintype "bidirectional"))
      (node (ref "U7") (pin "17") (pinfunction "SCK_17") (pintype "bidirectional"))
    )
    (net (code "108") (name "SPI2_MISO") (class "Default")
      (node (ref "U4") (pin "27") (pinfunction "PB14_27") (pintype "bidirectional"))
    )
    (net (code "109") (name "SPI2_MOSI") (class "Default")
      (node (ref "U4") (pin "28") (pinfunction "PB15_28") (pintype "bidirectional"))
    )
    (net (code "110") (name "SPI2_NSS") (class "Default")
      (node (ref "U4") (pin "25") (pinfunction "PB12_25") (pintype "bidirectional"))
    )
    (net (code "111") (name "SPI2_SCK") (class "Default")
      (node (ref "U4") (pin "26") (pinfunction "PB13_26") (pintype "bidirectional"))
    )
    (net (code "112") (name "SPI_MISO") (class "Default")
      (node (ref "JP1") (pin "4") (pinfunction "4_4") (pintype "passive"))
      (node (ref "U4") (pin "16") (pinfunction "PA6_16") (pintype "bidirectional"))
      (node (ref "U5") (pin "3") (pinfunction "HOST_MISO_3") (pintype "bidirectional"))
    )
    (net (code "113") (name "SPI_MOSI") (class "Default")
      (node (ref "JP1") (pin "5") (pinfunction "5_5") (pintype "passive"))
      (node (ref "U4") (pin "17") (pinfunction "PA7_17") (pintype "bidirectional"))
      (node (ref "U5") (pin "4") (pinfunction "HOST_MOSI_4") (pintype "bidirectional"))
    )
    (net (code "114") (name "SPI_NSS") (class "Default")
      (node (ref "JP1") (pin "2") (pinfunction "2_2") (pintype "passive"))
      (node (ref "U4") (pin "14") (pinfunction "PA4_14") (pintype "bidirectional"))
      (node (ref "U5") (pin "5") (pinfunction "HOST_CSN_5") (pintype "bidirectional"))
    )
    (net (code "115") (name "SPI_SCK") (class "Default")
      (node (ref "JP1") (pin "3") (pinfunction "3_3") (pintype "passive"))
      (node (ref "U4") (pin "15") (pinfunction "PA5_15") (pintype "bidirectional"))
      (node (ref "U5") (pin "2") (pinfunction "HOST_SCK_2") (pintype "bidirectional"))
    )
    (net (code "116") (name "SWCLK") (class "Default")
      (node (ref "U4") (pin "37") (pinfunction "PA14_37") (pintype "bidirectional"))
      (node (ref "X2") (pin "4") (pinfunction "S_4") (pintype "passive"))
    )
    (net (code "117") (name "SWDIO") (class "Default")
      (node (ref "U4") (pin "34") (pinfunction "PA13_34") (pintype "bidirectional"))
      (node (ref "X2") (pin "6") (pinfunction "S_6") (pintype "passive"))
    )
    (net (code "118") (name "TRACESWO") (class "Default")
      (node (ref "U4") (pin "39") (pinfunction "PB3_39") (pintype "bidirectional"))
      (node (ref "X2") (pin "2") (pinfunction "S_2") (pintype "passive"))
    )
    (net (code "119") (name "TX_ON") (class "Default")
      (node (ref "R16") (pin "1") (pinfunction "1_1") (pintype "passive"))
      (node (ref "U4") (pin "40") (pinfunction "PB4_40") (pintype "bidirectional"))
      (node (ref "U5") (pin "54") (pinfunction "GPIO[4]_54") (pintype "bidirectional"))
    )
    (net (code "120") (name "USB_DM") (class "Default")
      (node (ref "R1") (pin "2") (pinfunction "2_2") (pintype "passive"))
      (node (ref "U4") (pin "32") (pinfunction "PA11_32") (pintype "bidirectional"))
    )
    (net (code "121") (name "USB_DP") (class "Default")
      (node (ref "R2") (pin "2") (pinfunction "2_2") (pintype "passive"))
      (node (ref "U4") (pin "33") (pinfunction "PA12_33") (pintype "bidirectional"))
    )
    (net (code "122") (name "VCC") (class "Default")
      (node (ref "C36") (pin "1") (pinfunction "1_1") (pintype "passive"))
      (node (ref "C4") (pin "1") (pinfunction "1_1") (pintype "passive"))
      (node (ref "FB8") (pin "1") (pinfunction "1_1") (pintype "passive"))
      (node (ref "L2") (pin "1") (pinfunction "1_1") (pintype "passive"))
      (node (ref "U1") (pin "9") (pinfunction "VOUTB_9") (pintype "bidirectional"))
    )
    (net (code "123") (name "VCCA_A") (class "Default")
      (node (ref "C38") (pin "1") (pinfunction "1_1") (pintype "passive"))
      (node (ref "C45") (pin "1") (pinfunction "1_1") (pintype "passive"))
      (node (ref "C46") (pin "1") (pinfunction "1_1") (pintype "passive"))
      (node (ref "C60") (pin "1") (pinfunction "1_1") (pintype "passive"))
      (node (ref "C9") (pin "1") (pinfunction "1_1") (pintype "passive"))
      (node (ref "FB9") (pin "1") (pinfunction "1_1") (pintype "passive"))
      (node (ref "L6") (pin "2") (pinfunction "2_2") (pintype "passive"))
      (node (ref "U2") (pin "3") (pinfunction "OUTA_3") (pintype "bidirectional"))
      (node (ref "U6") (pin "16") (pinfunction "VBAT2_16") (pintype "bidirectional"))
      (node (ref "U6") (pin "2") (pinfunction "VBAT1_2") (pintype "bidirectional"))
      (node (ref "U6") (pin "32") (pinfunction "VBAT3_32") (pintype "bidirectional"))
    )
    (net (code "124") (name "VCCA_B") (class "Default")
      (node (ref "C11") (pin "1") (pinfunction "1_1") (pintype "passive"))
      (node (ref "C47") (pin "1") (pinfunction "1_1") (pintype "passive"))
      (node (ref "C53") (pin "1") (pinfunction "1_1") (pintype "passive"))
      (node (ref "C54") (pin "1") (pinfunction "1_1") (pintype "passive"))
      (node (ref "U2") (pin "1") (pinfunction "OUTB_1") (pintype "bidirectional"))
      (node (ref "U7") (pin "16") (pinfunction "VBAT2_16") (pintype "bidirectional"))
      (node (ref "U7") (pin "2") (pinfunction "VBAT1_2") (pintype "bidirectional"))
      (node (ref "U7") (pin "32") (pinfunction "VBAT3_32") (pintype "bidirectional"))
    )
    (net (code "125") (name "VCCDIG18") (class "Default")
      (node (ref "C25") (pin "1") (pinfunction "1_1") (pintype "passive"))
      (node (ref "C26") (pin "1") (pinfunction "1_1") (pintype "passive"))
      (node (ref "C27") (pin "1") (pinfunction "1_1") (pintype "passive"))
      (node (ref "C30") (pin "1") (pinfunction "1_1") (pintype "passive"))
      (node (ref "C35") (pin "1") (pinfunction "1_1") (pintype "passive"))
      (node (ref "C37") (pin "1") (pinfunction "1_1") (pintype "passive"))
      (node (ref "FB8") (pin "2") (pinfunction "2_2") (pintype "passive"))
      (node (ref "U5") (pin "12") (pinfunction "VCC18_12") (pintype "bidirectional"))
      (node (ref "U5") (pin "42") (pinfunction "VCC18_42") (pintype "bidirectional"))
      (node (ref "U5") (pin "60") (pinfunction "VCC18_60") (pintype "bidirectional"))
      (node (ref "U5") (pin "8") (pinfunction "VCC18_8") (pintype "bidirectional"))
    )
    (net (code "126") (name "VCCDIG33") (class "Default")
      (node (ref "C1") (pin "1") (pinfunction "1_1") (pintype "passive"))
      (node (ref "C23") (pin "1") (pinfunction "1_1") (pintype "passive"))
      (node (ref "C32") (pin "1") (pinfunction "1_1") (pintype "passive"))
      (node (ref "FB4") (pin "1") (pinfunction "1_1") (pintype "passive"))
      (node (ref "FB5") (pin "2") (pinfunction "2_2") (pintype "passive"))
      (node (ref "FB6") (pin "1") (pinfunction "1_1") (pintype "passive"))
      (node (ref "FB7") (pin "1") (pinfunction "1_1") (pintype "passive"))
      (node (ref "L1") (pin "2") (pinfunction "2_2") (pintype "passive"))
      (node (ref "U1") (pin "18") (pinfunction "VOUTA_18") (pintype "bidirectional"))
      (node (ref "U5") (pin "29") (pinfunction "VCC33_29") (pintype "bidirectional"))
    )
    (net (code "127") (name "VCCINT") (class "Default")
      (node (ref "C10") (pin "1") (pinfunction "1_1") (pintype "passive"))
      (node (ref "FB10") (pin "1") (pinfunction "1_1") (pintype "passive"))
      (node (ref "IC1") (pin "1") (pinfunction "VOUT_1") (pintype "bidirectional"))
      (node (ref "IC1") (pin "2") (pinfunction "VOUT_2") (pintype "bidirectional"))
      (node (ref "IC1") (pin "3") (pinfunction "SNS_3") (pintype "bidirectional"))
    )
    (net (code "128") (name "VCC_FEM") (class "Default")
      (node (ref "C58") (pin "1") (pinfunction "1_1") (pintype "passive"))
      (node (ref "C64") (pin "1") (pinfunction "1_1") (pintype "passive"))
      (node (ref "C66") (pin "1") (pinfunction "1_1") (pintype "passive"))
      (node (ref "FB10") (pin "2") (pinfunction "2_2") (pintype "passive"))
      (node (ref "L5") (pin "2") (pinfunction "2_2") (pintype "passive"))
      (node (ref "L7") (pin "1") (pinfunction "1_1") (pintype "passive"))
    )
    (net (code "129") (name "XTL_OUT") (class "Default")
      (node (ref "C40") (pin "2") (pinfunction "2_2") (pintype "passive"))
      (node (ref "C48") (pin "2") (pinfunction "2_2") (pintype "passive"))
      (node (ref "X4") (pin "3") (pinfunction "OUT_3") (pintype "bidirectional"))
    )
    (net (code "130") (name "unconnected-(U2-PGOOD-Pad8)") (class "Default")
      (node (ref "U2") (pin "8") (pinfunction "PGOOD_8") (pintype "bidirectional"))
    )
    (net (code "131") (name "unconnected-(U4-PA1-Pad11)") (class "Default")
      (node (ref "U4") (pin "11") (pinfunction "PA1_11") (pintype "bidirectional"))
    )
    (net (code "132") (name "unconnected-(U4-PA15-Pad38)") (class "Default")
      (node (ref "U4") (pin "38") (pinfunction "PA15_38") (pintype "bidirectional"))
    )
    (net (code "133") (name "unconnected-(U4-PC13-Pad2)") (class "Default")
      (node (ref "U4") (pin "2") (pinfunction "PC13_2") (pintype "bidirectional"))
    )
    (net (code "134") (name "unconnected-(U4-PC14-OSC32_IN-Pad3)") (class "Default")
      (node (ref "U4") (pin "3") (pinfunction "PC14-OSC32_IN_3") (pintype "bidirectional"))
    )
    (net (code "135") (name "unconnected-(U4-PC15-OSC32_OUT-Pad4)") (class "Default")
      (node (ref "U4") (pin "4") (pinfunction "PC15-OSC32_OUT_4") (pintype "bidirectional"))
    )
    (net (code "136") (name "unconnected-(U4-PH1-OSC_OUT-Pad6)") (class "Default")
      (node (ref "U4") (pin "6") (pinfunction "PH1-OSC_OUT_6") (pintype "bidirectional"))
    )
    (net (code "137") (name "unconnected-(U5-B_IQ_TX-Pad37)") (class "Default")
      (node (ref "U5") (pin "37") (pinfunction "B_IQ_TX_37") (pintype "bidirectional"))
    )
    (net (code "138") (name "unconnected-(U5-B_QI_TX-Pad38)") (class "Default")
      (node (ref "U5") (pin "38") (pinfunction "B_QI_TX_38") (pintype "bidirectional"))
    )
    (net (code "139") (name "unconnected-(U5-LNA_B_CTRL-Pad27)") (class "Default")
      (node (ref "U5") (pin "27") (pinfunction "LNA_B_CTRL_27") (pintype "bidirectional"))
    )
    (net (code "140") (name "unconnected-(U5-PA_B_CTRL-Pad26)") (class "Default")
      (node (ref "U5") (pin "26") (pinfunction "PA_B_CTRL_26") (pintype "bidirectional"))
    )
    (net (code "141") (name "unconnected-(U5-PA_GAIN[0]-Pad18)") (class "Default")
      (node (ref "U5") (pin "18") (pinfunction "PA_GAIN[0]_18") (pintype "bidirectional"))
    )
    (net (code "142") (name "unconnected-(U5-PA_GAIN[1]-Pad17)") (class "Default")
      (node (ref "U5") (pin "17") (pinfunction "PA_GAIN[1]_17") (pintype "bidirectional"))
    )
    (net (code "143") (name "unconnected-(U5-RADIO_A_EN-Pad13)") (class "Default")
      (node (ref "U5") (pin "13") (pinfunction "RADIO_A_EN_13") (pintype "bidirectional"))
    )
    (net (code "144") (name "unconnected-(U5-RADIO_B_EN-Pad28)") (class "Default")
      (node (ref "U5") (pin "28") (pinfunction "RADIO_B_EN_28") (pintype "bidirectional"))
    )
    (net (code "145") (name "unconnected-(U5-RADIO_RST-Pad25)") (class "Default")
      (node (ref "U5") (pin "25") (pinfunction "RADIO_RST_25") (pintype "bidirectional"))
    )
    (net (code "146") (name "unconnected-(U6-CLK_OUT-Pad10)") (class "Default")
      (node (ref "U6") (pin "10") (pinfunction "CLK_OUT_10") (pintype "bidirectional"))
    )
    (net (code "147") (name "unconnected-(U6-DIO0-Pad21)") (class "Default")
      (node (ref "U6") (pin "21") (pinfunction "DIO0_21") (pintype "bidirectional"))
    )
    (net (code "148") (name "unconnected-(U6-DIO1-Pad22)") (class "Default")
      (node (ref "U6") (pin "22") (pinfunction "DIO1_22") (pintype "bidirectional"))
    )
    (net (code "149") (name "unconnected-(U6-DIO2-Pad23)") (class "Default")
      (node (ref "U6") (pin "23") (pinfunction "DIO2_23") (pintype "bidirectional"))
    )
    (net (code "150") (name "unconnected-(U6-DIO3-Pad24)") (class "Default")
      (node (ref "U6") (pin "24") (pinfunction "DIO3_24") (pintype "bidirectional"))
    )
    (net (code "151") (name "unconnected-(U6-XTA-Pad6)") (class "Default")
      (node (ref "U6") (pin "6") (pinfunction "XTA_6") (pintype "bidirectional"))
    )
    (net (code "152") (name "unconnected-(U7-CLK_IN-Pad11)") (class "Default")
      (node (ref "U7") (pin "11") (pinfunction "CLK_IN_11") (pintype "bidirectional"))
    )
    (net (code "153") (name "unconnected-(U7-DIO0-Pad21)") (class "Default")
      (node (ref "U7") (pin "21") (pinfunction "DIO0_21") (pintype "bidirectional"))
    )
    (net (code "154") (name "unconnected-(U7-DIO1-Pad22)") (class "Default")
      (node (ref "U7") (pin "22") (pinfunction "DIO1_22") (pintype "bidirectional"))
    )
    (net (code "155") (name "unconnected-(U7-DIO2-Pad23)") (class "Default")
      (node (ref "U7") (pin "23") (pinfunction "DIO2_23") (pintype "bidirectional"))
    )
    (net (code "156") (name "unconnected-(U7-DIO3-Pad24)") (class "Default")
      (node (ref "U7") (pin "24") (pinfunction "DIO3_24") (pintype "bidirectional"))
    )
    (net (code "157") (name "unconnected-(U7-RF_ON-Pad29)") (class "Default")
      (node (ref "U7") (pin "29") (pinfunction "RF_ON_29") (pintype "bidirectional"))
    )
    (net (code "158") (name "unconnected-(U7-RF_OP-Pad30)") (class "Default")
      (node (ref "U7") (pin "30") (pinfunction "RF_OP_30") (pintype "bidirectional"))
    )
    (net (code "159") (name "unconnected-(U7-XTA-Pad6)") (class "Default")
      (node (ref "U7") (pin "6") (pinfunction "XTA_6") (pintype "bidirectional"))
    )
    (net (code "160") (name "unconnected-(U10-N{slash}C-Pad19)") (class "Default")
      (node (ref "U10") (pin "19") (pinfunction "N/C_19") (pintype "bidirectional"))
    )
    (net (code "161") (name "unconnected-(U10-N{slash}C-Pad22)") (class "Default")
      (node (ref "U10") (pin "22") (pinfunction "N/C_22") (pintype "bidirectional"))
    )
    (net (code "162") (name "unconnected-(X1-ID-Pad4)") (class "Default")
      (node (ref "X1") (pin "4") (pinfunction "ID_4") (pintype "bidirectional"))
    )
  )
)
